# Titan_v1p2.net
KiCad netlist of a schematic drawn in EAGLE
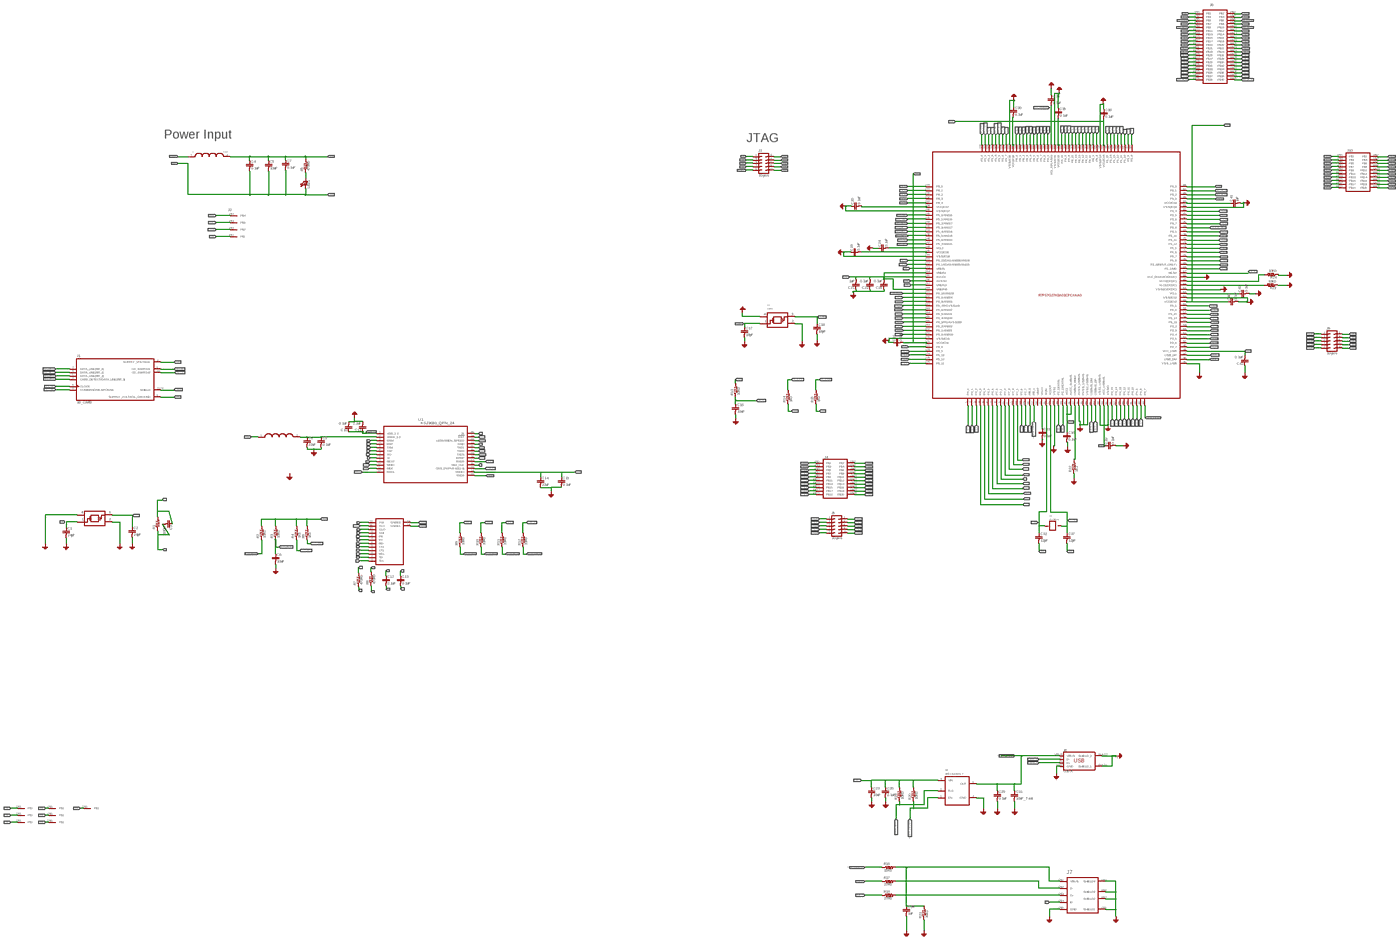
[diagram p0: schematic, sheet 1, overview]
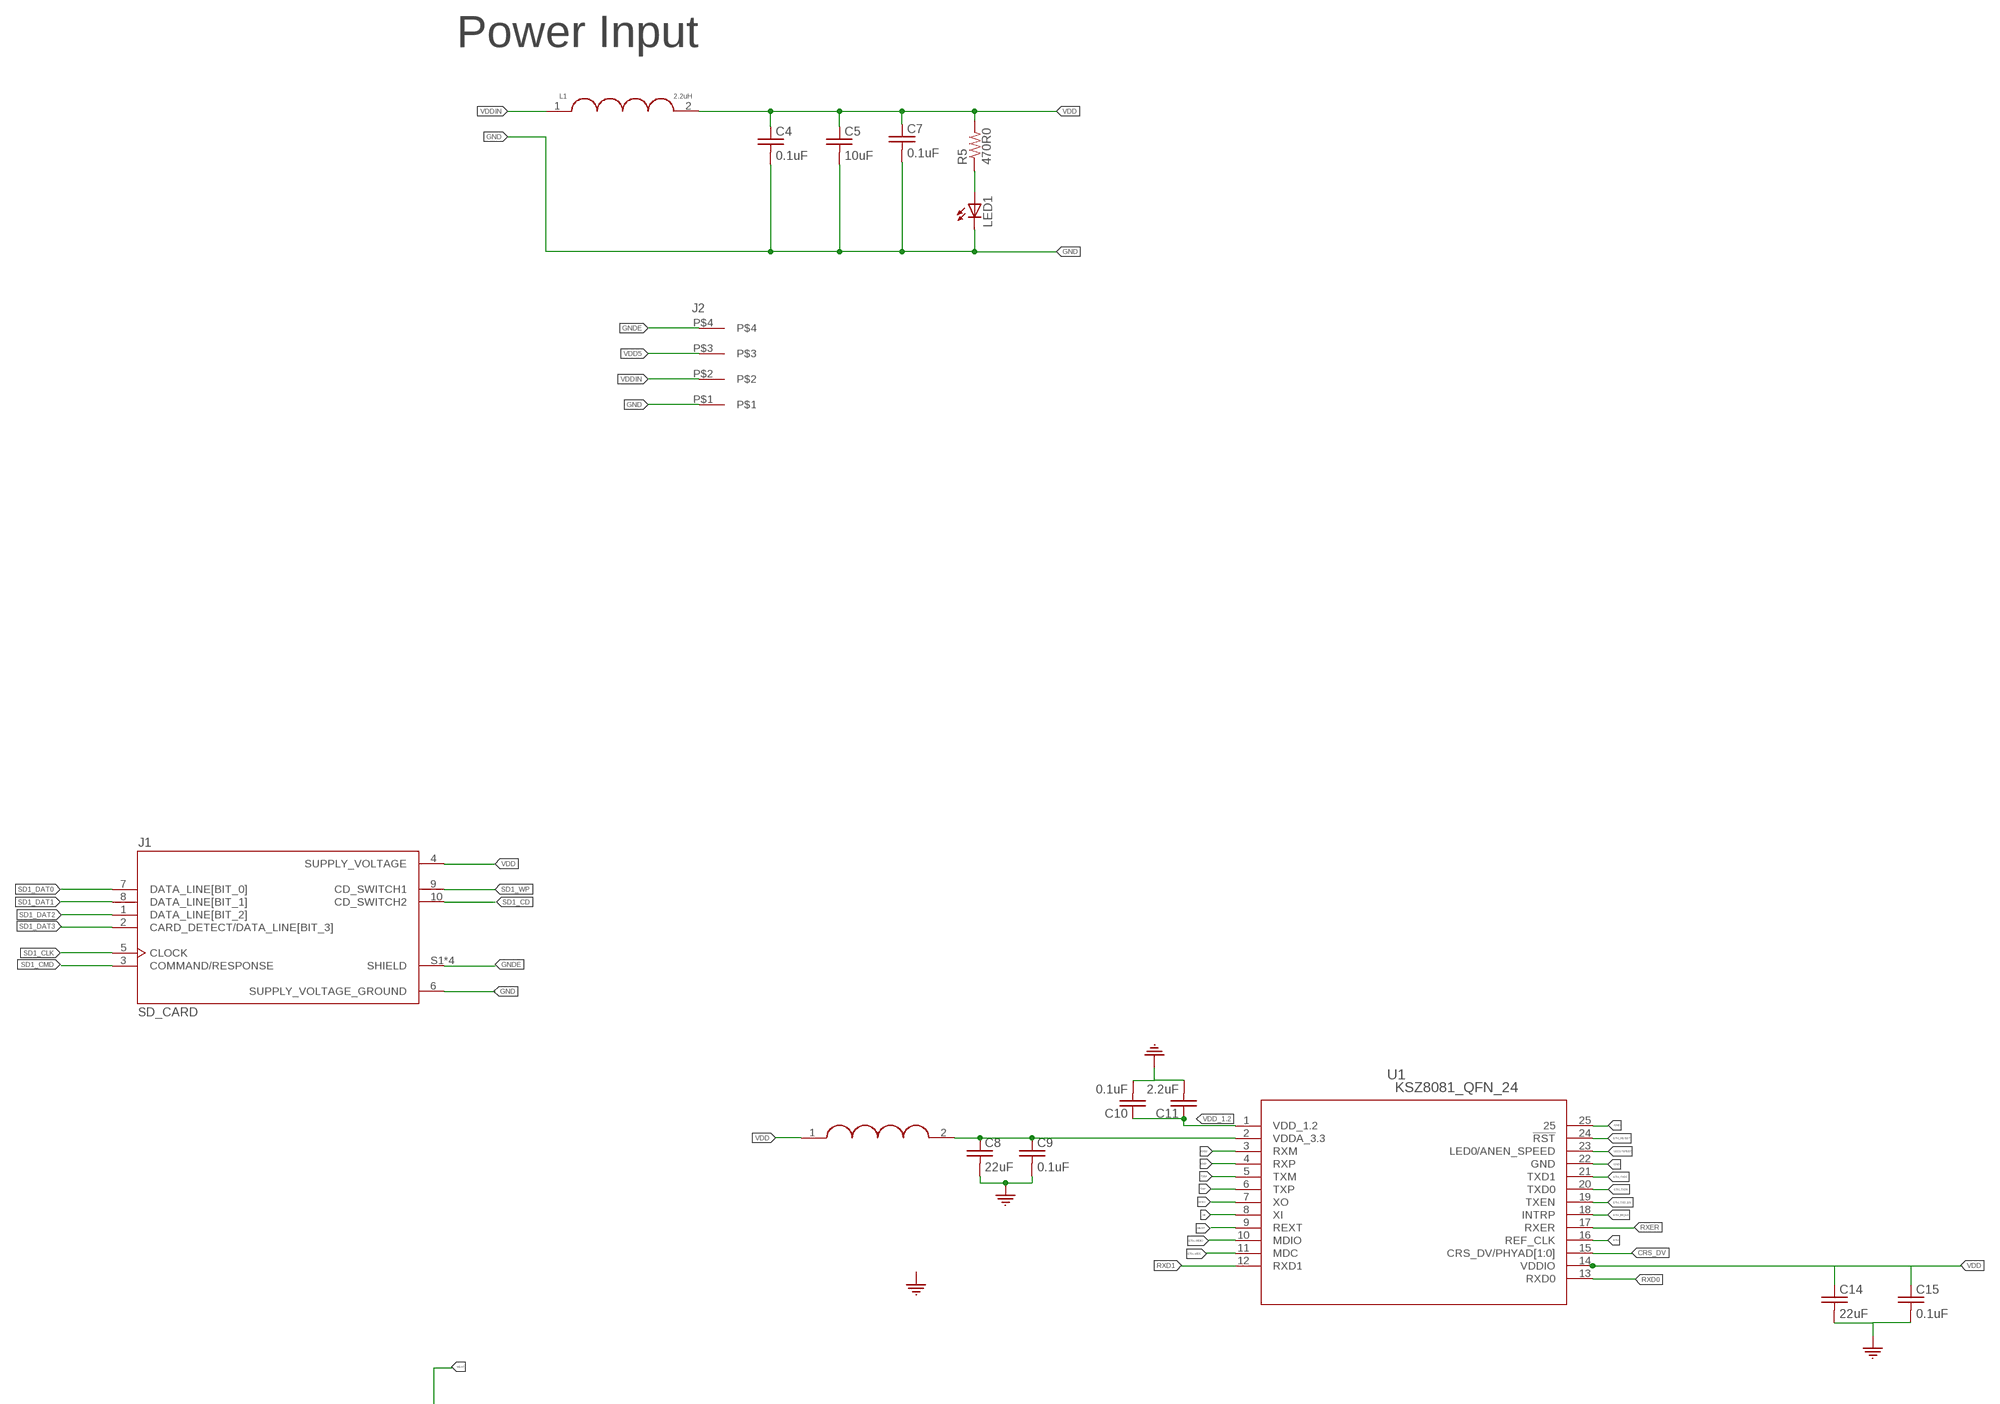
[diagram p1: schematic, sheet 1, part 1 of 5]
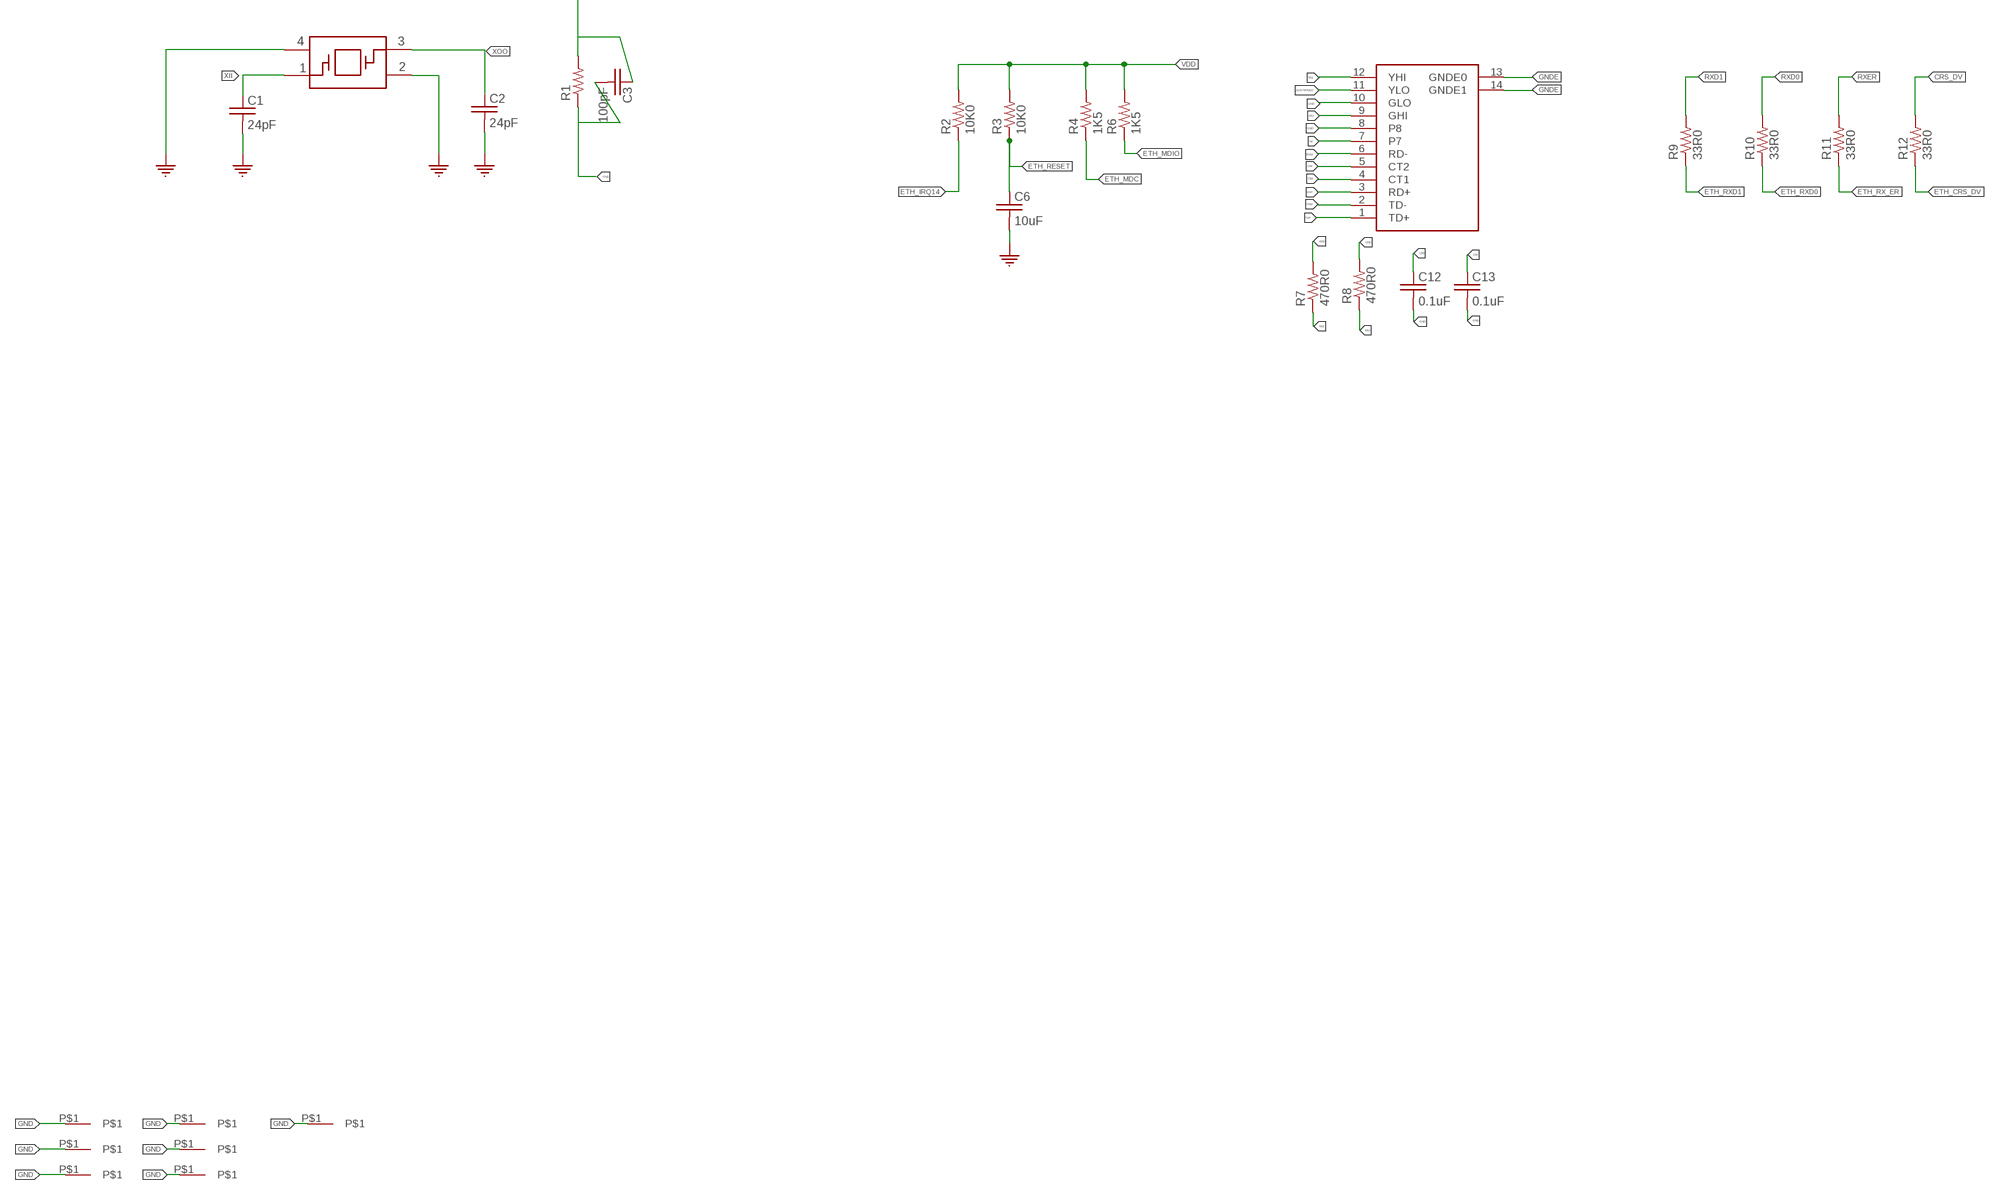
[diagram p2: schematic, sheet 1, part 2 of 5]
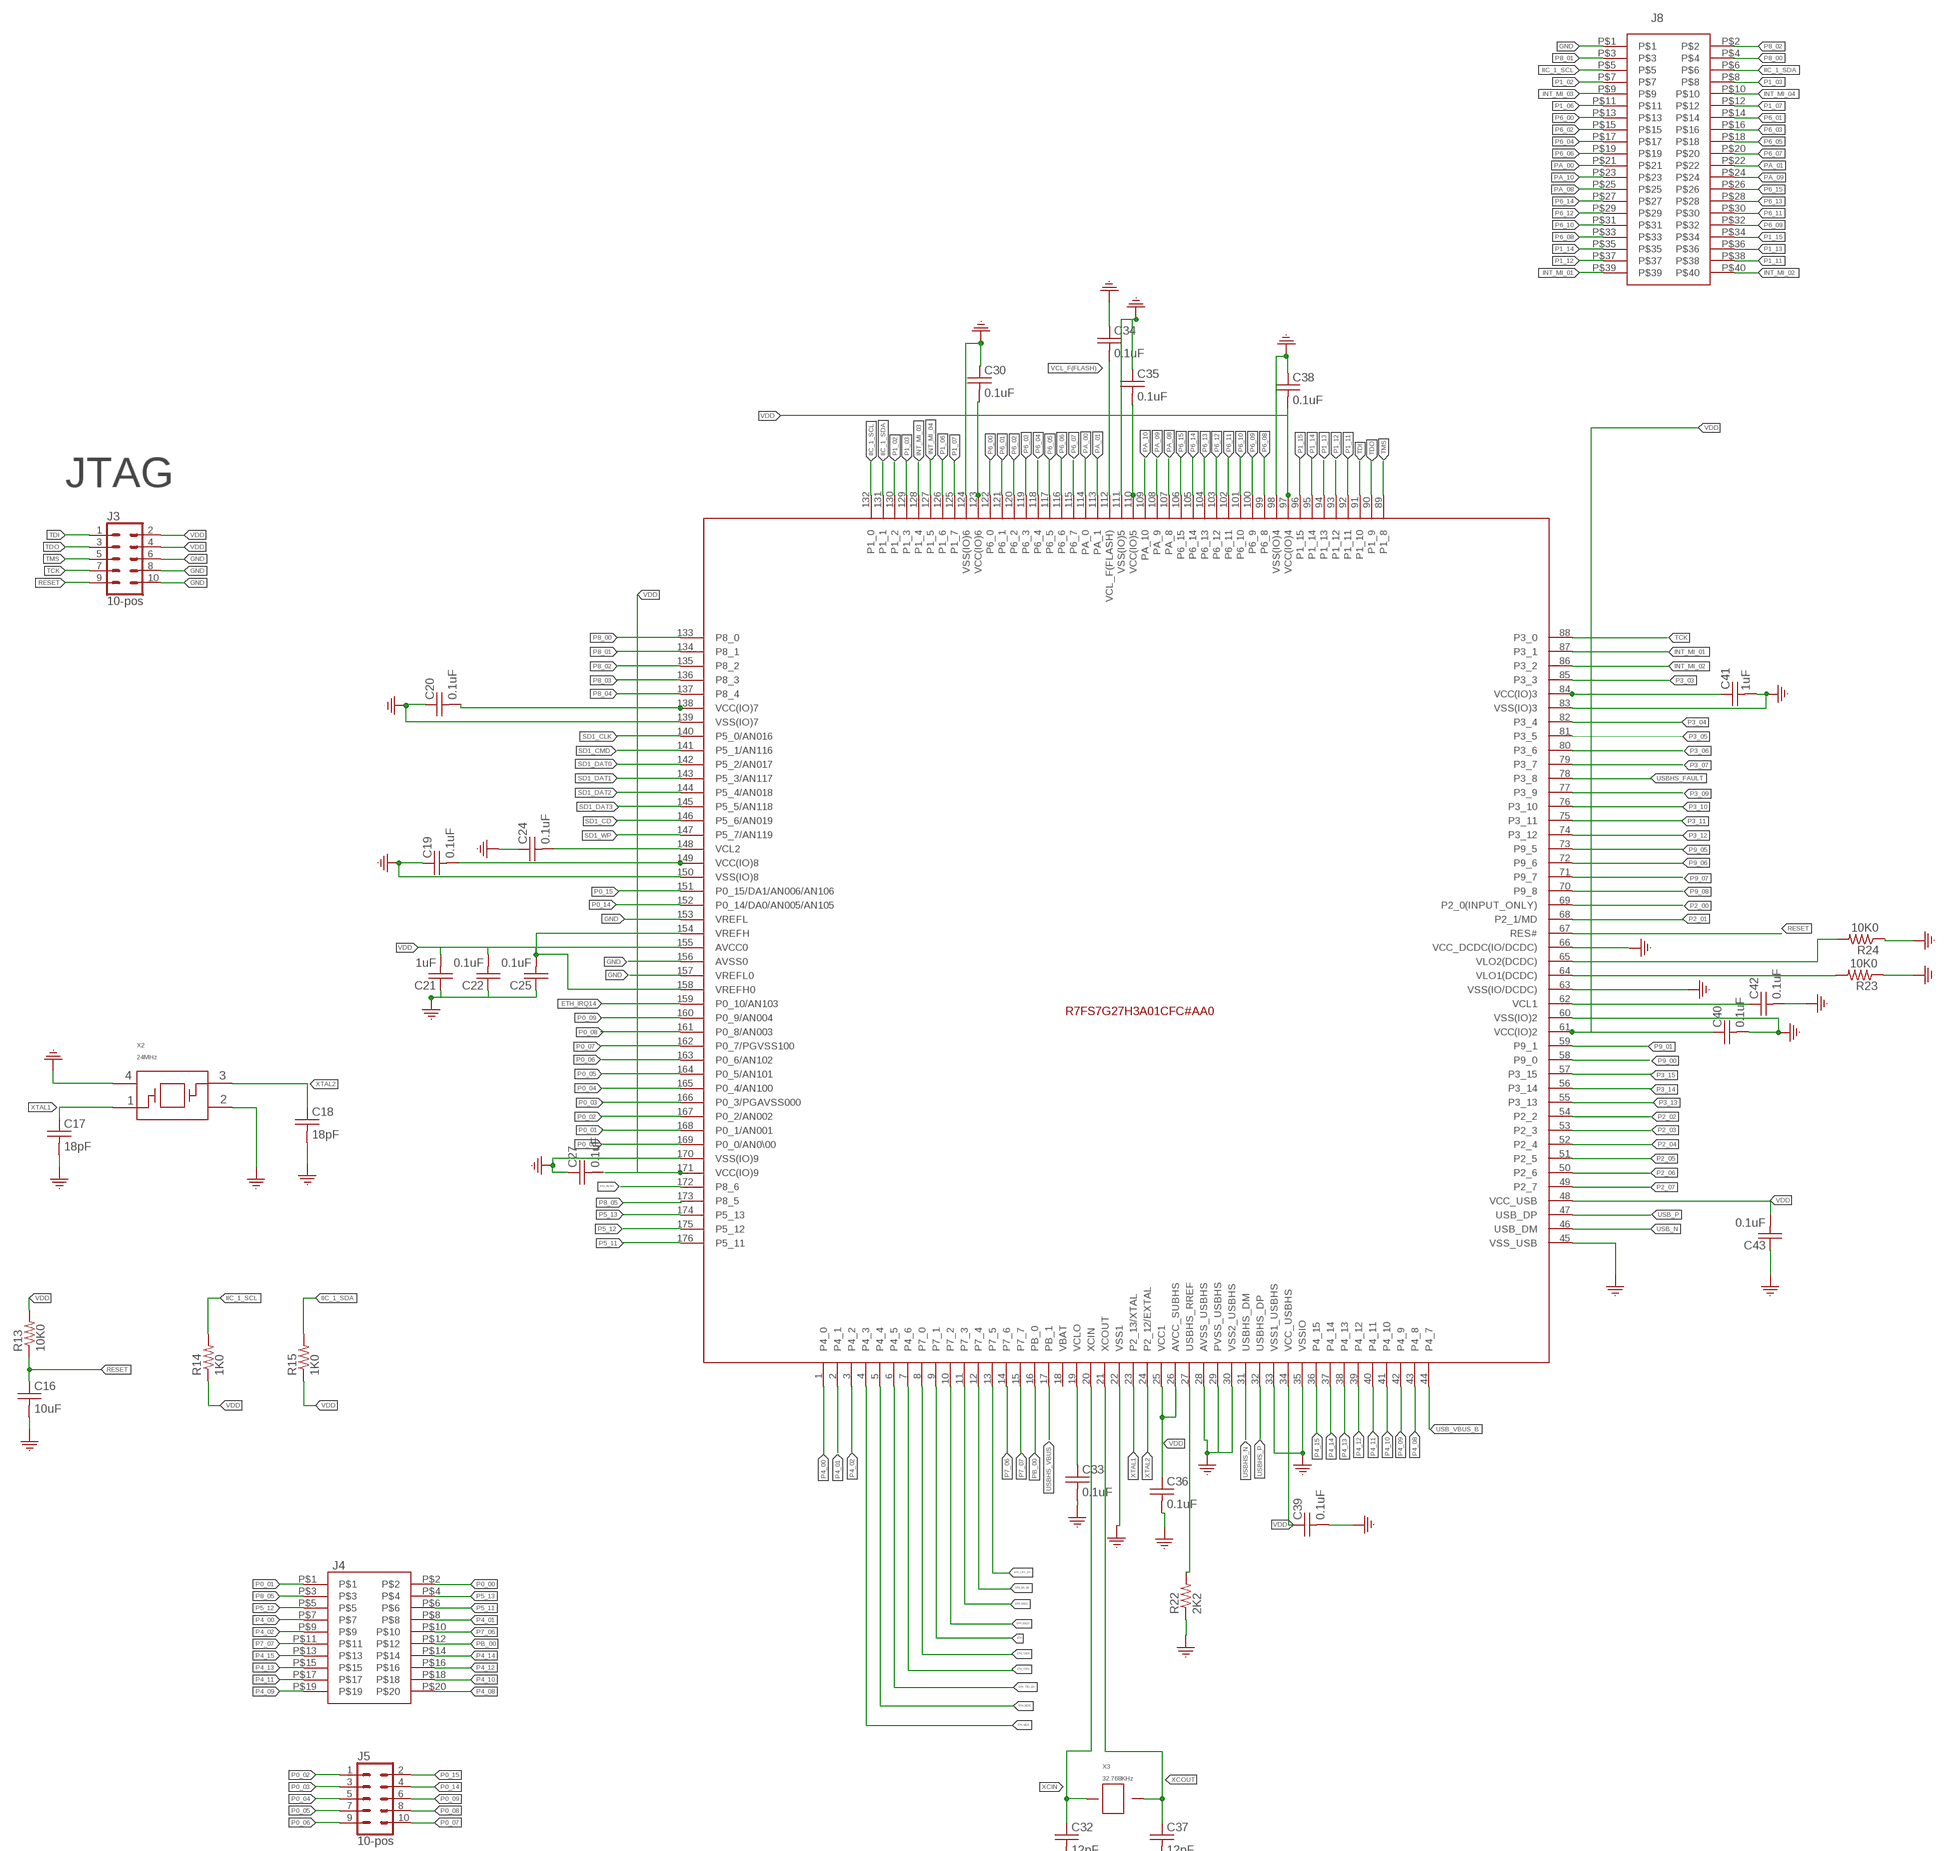
[diagram p3: schematic, sheet 1, part 3 of 5]
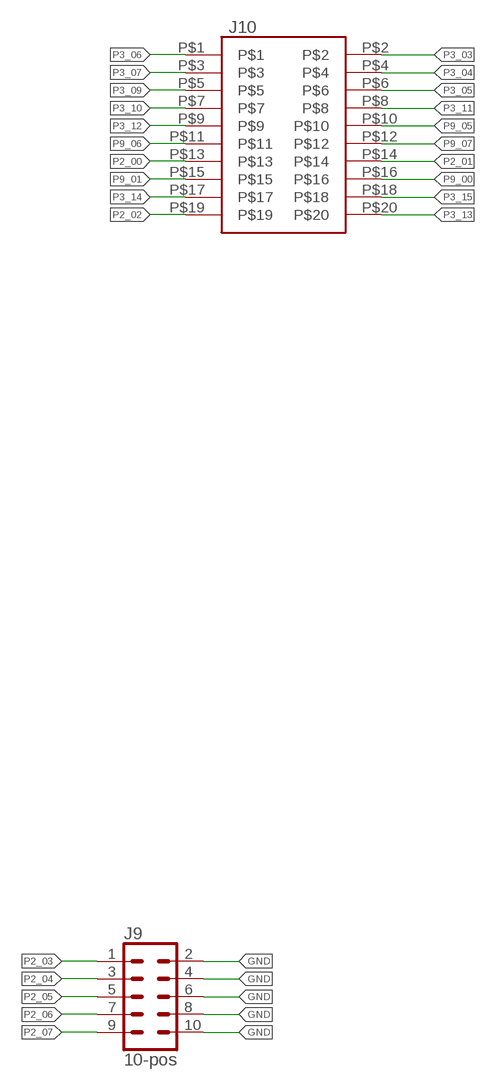
[diagram p4: schematic, sheet 1, part 4 of 5]
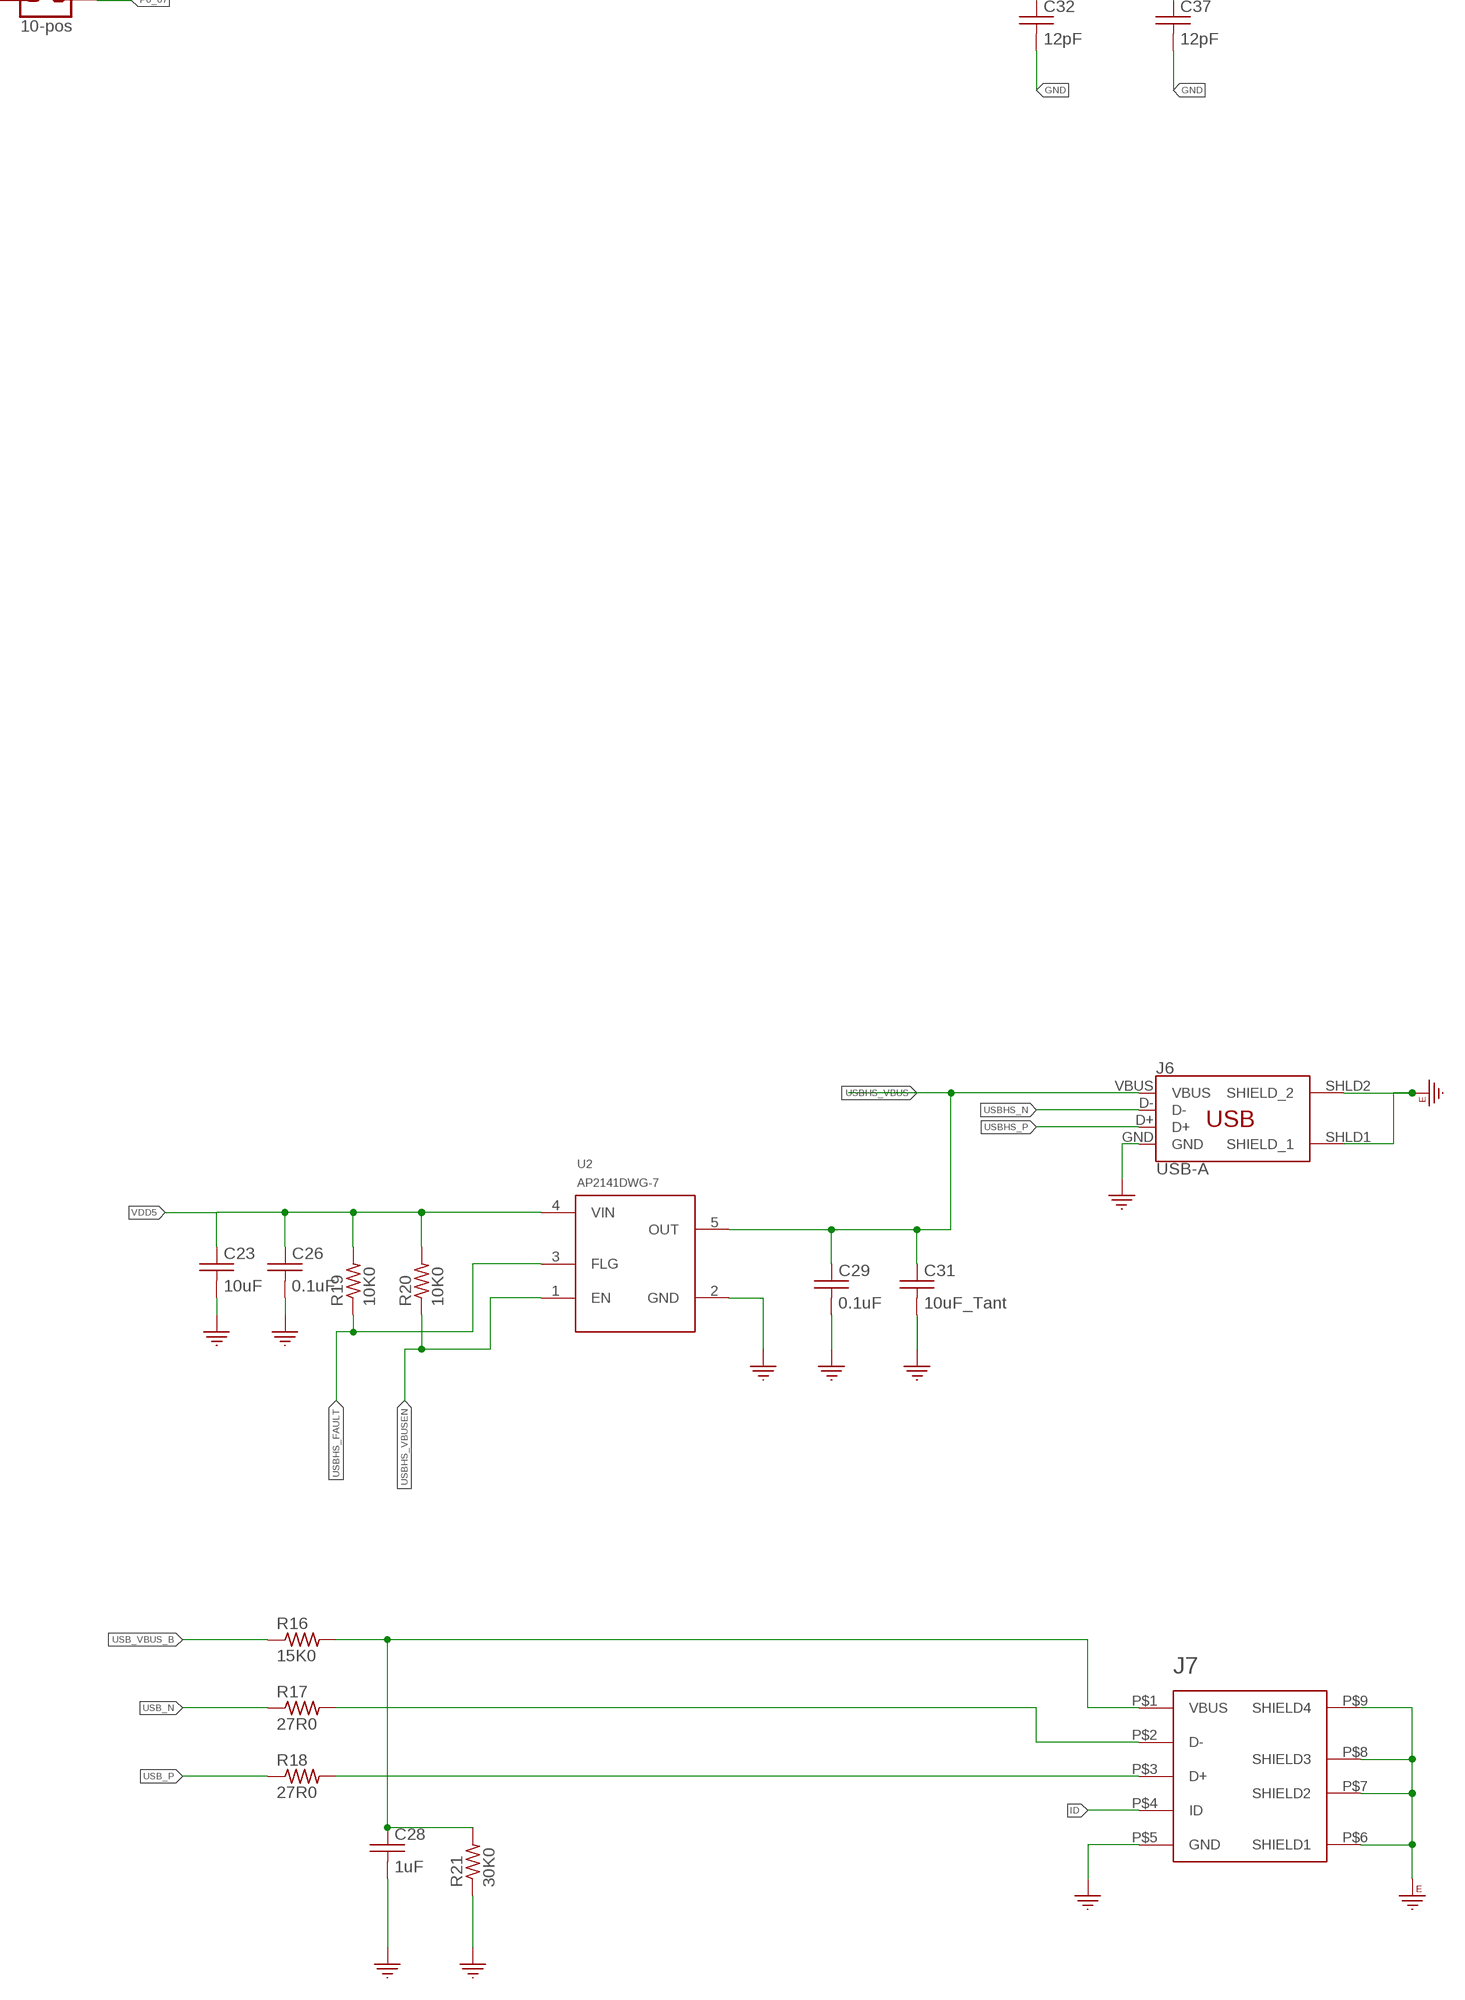
[diagram p5: schematic, sheet 1, part 5 of 5]

(export (version "E")
  (design (tool "Eeschema 10.0.6"))
  (components
    (comp (ref "C1")
      (value "24pF")
      (footprint "eagle-import:0402")
      (fields (field (name "PARTNO") "CC0402GRNPO9BN240"))
      (libsource (lib "eagle-import") (part "C_0402_24PF"))
    )
    (comp (ref "C2")
      (value "24pF")
      (footprint "eagle-import:0402")
      (fields (field (name "PARTNO") "CC0402GRNPO9BN240"))
      (libsource (lib "eagle-import") (part "C_0402_24PF"))
    )
    (comp (ref "C3")
      (value "100pF")
      (footprint "eagle-import:0402")
      (fields (field (name "PARTNO") "CL05C101JB5NNNC"))
      (libsource (lib "eagle-import") (part "C_0402_100PF"))
    )
    (comp (ref "C4")
      (value "0.1uF")
      (footprint "eagle-import:0402")
      (fields (field (name "PARTNO") "CL05F104ZO5NNNC"))
      (libsource (lib "eagle-import") (part "C_0402_0.1UF"))
    )
    (comp (ref "C5")
      (value "10uF")
      (footprint "eagle-import:0402")
      (fields (field (name "PARTNO") "CL05A106MP8NUB8"))
      (libsource (lib "eagle-import") (part "C_0402_10UF"))
    )
    (comp (ref "C6")
      (value "10uF")
      (footprint "eagle-import:0402")
      (fields (field (name "PARTNO") "CL05A106MP8NUB8"))
      (libsource (lib "eagle-import") (part "C_0402_10UF"))
    )
    (comp (ref "C7")
      (value "0.1uF")
      (footprint "eagle-import:0402")
      (fields (field (name "PARTNO") "CL05F104ZO5NNNC"))
      (libsource (lib "eagle-import") (part "C_0402_0.1UF"))
    )
    (comp (ref "C8")
      (value "22uF")
      (footprint "eagle-import:0402")
      (fields (field (name "PARTNO") "CL05A226MQ5N6J8"))
      (libsource (lib "eagle-import") (part "C_0402_22UF"))
    )
    (comp (ref "C9")
      (value "0.1uF")
      (footprint "eagle-import:0402")
      (fields (field (name "PARTNO") "CL05F104ZO5NNNC"))
      (libsource (lib "eagle-import") (part "C_0402_0.1UF"))
    )
    (comp (ref "C10")
      (value "0.1uF")
      (footprint "eagle-import:0402")
      (fields (field (name "PARTNO") "CL05F104ZO5NNNC"))
      (libsource (lib "eagle-import") (part "C_0402_0.1UF"))
    )
    (comp (ref "C11")
      (value "2.2uF")
      (footprint "eagle-import:0402")
      (fields (field (name "PARTNO") "GRM155C81C225ME15D"))
      (libsource (lib "eagle-import") (part "C_0402_2.2UF"))
    )
    (comp (ref "C12")
      (value "0.1uF")
      (footprint "eagle-import:0402")
      (fields (field (name "PARTNO") "CL05F104ZO5NNNC"))
      (libsource (lib "eagle-import") (part "C_0402_0.1UF"))
    )
    (comp (ref "C13")
      (value "0.1uF")
      (footprint "eagle-import:0402")
      (fields (field (name "PARTNO") "CL05F104ZO5NNNC"))
      (libsource (lib "eagle-import") (part "C_0402_0.1UF"))
    )
    (comp (ref "C14")
      (value "22uF")
      (footprint "eagle-import:0402")
      (fields (field (name "PARTNO") "CL05A226MQ5N6J8"))
      (libsource (lib "eagle-import") (part "C_0402_22UF"))
    )
    (comp (ref "C15")
      (value "0.1uF")
      (footprint "eagle-import:0402")
      (fields (field (name "PARTNO") "CL05F104ZO5NNNC"))
      (libsource (lib "eagle-import") (part "C_0402_0.1UF"))
    )
    (comp (ref "C16")
      (value "10uF")
      (footprint "eagle-import:0402")
      (fields (field (name "PARTNO") "CL05A106MP8NUB8"))
      (libsource (lib "eagle-import") (part "C_0402_10UF"))
    )
    (comp (ref "C17")
      (value "18pF")
      (footprint "eagle-import:0402")
      (fields (field (name "PARTNO") "UMK105CG180JV-F"))
      (libsource (lib "eagle-import") (part "C_0402_18PF"))
    )
    (comp (ref "C18")
      (value "18pF")
      (footprint "eagle-import:0402")
      (fields (field (name "PARTNO") "UMK105CG180JV-F"))
      (libsource (lib "eagle-import") (part "C_0402_18PF"))
    )
    (comp (ref "C19")
      (value "0.1uF")
      (footprint "eagle-import:0402")
      (fields (field (name "PARTNO") "CL05F104ZO5NNNC"))
      (libsource (lib "eagle-import") (part "C_0402_0.1UF"))
    )
    (comp (ref "C20")
      (value "0.1uF")
      (footprint "eagle-import:0402")
      (fields (field (name "PARTNO") "CL05F104ZO5NNNC"))
      (libsource (lib "eagle-import") (part "C_0402_0.1UF"))
    )
    (comp (ref "C21")
      (value "1uF")
      (footprint "eagle-import:0402")
      (fields (field (name "PARTNO") "CL05A105KO5NNNC"))
      (libsource (lib "eagle-import") (part "C_0402_1UF"))
    )
    (comp (ref "C22")
      (value "0.1uF")
      (footprint "eagle-import:0402")
      (fields (field (name "PARTNO") "CL05F104ZO5NNNC"))
      (libsource (lib "eagle-import") (part "C_0402_0.1UF"))
    )
    (comp (ref "C23")
      (value "10uF")
      (footprint "eagle-import:0402")
      (fields (field (name "PARTNO") "CL05A106MP8NUB8"))
      (libsource (lib "eagle-import") (part "C_0402_10UF"))
    )
    (comp (ref "C24")
      (value "0.1uF")
      (footprint "eagle-import:0402")
      (fields (field (name "PARTNO") "CL05F104ZO5NNNC"))
      (libsource (lib "eagle-import") (part "C_0402_0.1UF"))
    )
    (comp (ref "C25")
      (value "0.1uF")
      (footprint "eagle-import:0402")
      (fields (field (name "PARTNO") "CL05F104ZO5NNNC"))
      (libsource (lib "eagle-import") (part "C_0402_0.1UF"))
    )
    (comp (ref "C26")
      (value "0.1uF")
      (footprint "eagle-import:0402")
      (fields (field (name "PARTNO") "CL05F104ZO5NNNC"))
      (libsource (lib "eagle-import") (part "C_0402_0.1UF"))
    )
    (comp (ref "C27")
      (value "0.1uF")
      (footprint "eagle-import:0402")
      (fields (field (name "PARTNO") "CL05F104ZO5NNNC"))
      (libsource (lib "eagle-import") (part "C_0402_0.1UF"))
    )
    (comp (ref "C28")
      (value "1uF")
      (footprint "eagle-import:0402")
      (fields (field (name "PARTNO") "CL05A105KO5NNNC"))
      (libsource (lib "eagle-import") (part "C_0402_1UF"))
    )
    (comp (ref "C29")
      (value "0.1uF")
      (footprint "eagle-import:0402")
      (fields (field (name "PARTNO") "CL05F104ZO5NNNC"))
      (libsource (lib "eagle-import") (part "C_0402_0.1UF"))
    )
    (comp (ref "C30")
      (value "0.1uF")
      (footprint "eagle-import:0402")
      (fields (field (name "PARTNO") "CL05F104ZO5NNNC"))
      (libsource (lib "eagle-import") (part "C_0402_0.1UF"))
    )
    (comp (ref "C31")
      (value "10uF_Tant")
      (footprint "eagle-import:C1210")
      (fields (field (name "PARTNO") "TPST106K016H0800"))
      (libsource (lib "eagle-import") (part "C_1210_10UF_TANT"))
    )
    (comp (ref "C32")
      (value "12pF")
      (footprint "eagle-import:0402")
      (fields (field (name "PARTNO") "CL05C120JB5NNNC"))
      (libsource (lib "eagle-import") (part "C_0402_12PF"))
    )
    (comp (ref "C33")
      (value "0.1uF")
      (footprint "eagle-import:0402")
      (fields (field (name "PARTNO") "CL05F104ZO5NNNC"))
      (libsource (lib "eagle-import") (part "C_0402_0.1UF"))
    )
    (comp (ref "C34")
      (value "0.1uF")
      (footprint "eagle-import:0402")
      (fields (field (name "PARTNO") "CL05F104ZO5NNNC"))
      (libsource (lib "eagle-import") (part "C_0402_0.1UF"))
    )
    (comp (ref "C35")
      (value "0.1uF")
      (footprint "eagle-import:0402")
      (fields (field (name "PARTNO") "CL05F104ZO5NNNC"))
      (libsource (lib "eagle-import") (part "C_0402_0.1UF"))
    )
    (comp (ref "C36")
      (value "0.1uF")
      (footprint "eagle-import:0402")
      (fields (field (name "PARTNO") "CL05F104ZO5NNNC"))
      (libsource (lib "eagle-import") (part "C_0402_0.1UF"))
    )
    (comp (ref "C37")
      (value "12pF")
      (footprint "eagle-import:0402")
      (fields (field (name "PARTNO") "CL05C120JB5NNNC"))
      (libsource (lib "eagle-import") (part "C_0402_12PF"))
    )
    (comp (ref "C38")
      (value "0.1uF")
      (footprint "eagle-import:0402")
      (fields (field (name "PARTNO") "CL05F104ZO5NNNC"))
      (libsource (lib "eagle-import") (part "C_0402_0.1UF"))
    )
    (comp (ref "C39")
      (value "0.1uF")
      (footprint "eagle-import:0402")
      (fields (field (name "PARTNO") "CL05F104ZO5NNNC"))
      (libsource (lib "eagle-import") (part "C_0402_0.1UF"))
    )
    (comp (ref "C40")
      (value "0.1uF")
      (footprint "eagle-import:0402")
      (fields (field (name "PARTNO") "CL05F104ZO5NNNC"))
      (libsource (lib "eagle-import") (part "C_0402_0.1UF"))
    )
    (comp (ref "C41")
      (value "1uF")
      (footprint "eagle-import:0402")
      (fields (field (name "PARTNO") "CL05A105KO5NNNC"))
      (libsource (lib "eagle-import") (part "C_0402_1UF"))
    )
    (comp (ref "C42")
      (value "0.1uF")
      (footprint "eagle-import:0402")
      (fields (field (name "PARTNO") "CL05F104ZO5NNNC"))
      (libsource (lib "eagle-import") (part "C_0402_0.1UF"))
    )
    (comp (ref "C43")
      (value "0.1uF")
      (footprint "eagle-import:0402")
      (fields (field (name "PARTNO") "CL05F104ZO5NNNC"))
      (libsource (lib "eagle-import") (part "C_0402_0.1UF"))
    )
    (comp (ref "FB1")
      (value "FB2_603")
      (footprint "eagle-import:0603")
      (fields (field (name "PARTNO") "BLM18PG121SN1D"))
      (libsource (lib "eagle-import") (part "FB_0603_120_OHM0603"))
    )
    (comp (ref "FID1")
      (value "FIDUCIAL")
      (footprint "eagle-import:FIDUCIAL")
      (libsource (lib "eagle-import") (part "FIDUCIAL"))
    )
    (comp (ref "FID2")
      (value "FIDUCIAL")
      (footprint "eagle-import:FIDUCIAL")
      (libsource (lib "eagle-import") (part "FIDUCIAL"))
    )
    (comp (ref "FID3")
      (value "FIDUCIAL")
      (footprint "eagle-import:FIDUCIAL")
      (libsource (lib "eagle-import") (part "FIDUCIAL"))
    )
    (comp (ref "FID4")
      (value "FIDUCIAL")
      (footprint "eagle-import:FIDUCIAL")
      (libsource (lib "eagle-import") (part "FIDUCIAL"))
    )
    (comp (ref "FID5")
      (value "FIDUCIAL")
      (footprint "eagle-import:FIDUCIAL")
      (libsource (lib "eagle-import") (part "FIDUCIAL"))
    )
    (comp (ref "FID6")
      (value "FIDUCIAL")
      (footprint "eagle-import:FIDUCIAL")
      (libsource (lib "eagle-import") (part "FIDUCIAL"))
    )
    (comp (ref "FID7")
      (value "FIDUCIAL")
      (footprint "eagle-import:FIDUCIAL")
      (libsource (lib "eagle-import") (part "FIDUCIAL"))
    )
    (comp (ref "J1")
      (value "SD_CARD")
      (footprint "eagle-import:SD_CARD")
      (fields (field (name "MF") "Amphenol ICC") (field (name "PARTNO") "114-00841-68"))
      (libsource (lib "eagle-import") (part "SD_CARD_1140084168"))
    )
    (comp (ref "J2")
      (value "4-pos")
      (footprint "eagle-import:1X4_3.81MM_PITCH")
      (fields (field (name "PARTNO") "691322310004"))
      (libsource (lib "eagle-import") (part "3.81MM_1_X_4_RT_ANGLE_PLUG_HEADER"))
    )
    (comp (ref "J3")
      (value "10-pos")
      (footprint "eagle-import:2X5")
      (fields (field (name "PARTNO") "PH2RA-10-UA"))
      (libsource (lib "eagle-import") (part "CONN_05X2_RAPTH"))
    )
    (comp (ref "J4")
      (value "20-pos")
      (footprint "eagle-import:2_X_10_.1_INCH")
      (fields (field (name "PARTNO") "67996-420HLF"))
      (libsource (lib "eagle-import") (part "2_X_10_HEADER_GENERIC"))
    )
    (comp (ref "J5")
      (value "10-pos")
      (footprint "eagle-import:2X5")
      (fields (field (name "PARTNO") "PH2RA-10-UA"))
      (libsource (lib "eagle-import") (part "CONN_05X2_RAPTH"))
    )
    (comp (ref "J6")
      (value "USB-A")
      (footprint "eagle-import:USB_A_SMT")
      (fields (field (name "PARTNO") "87583-3010RPALF"))
      (libsource (lib "eagle-import") (part "USB_A"))
    )
    (comp (ref "J7")
      (value "USB-B-Micro")
      (footprint "eagle-import:USB_MICRO-B")
      (fields (field (name "PARTNO") "10118192-0002LF"))
      (libsource (lib "eagle-import") (part "USB_MICRO-B"))
    )
    (comp (ref "J8")
      (value "40-pos")
      (footprint "eagle-import:HEADER_2_X_20_.1_INCH")
      (fields (field (name "PARTNO") "61304021021"))
      (libsource (lib "eagle-import") (part "HEADER_2_X_20_GENERIC"))
    )
    (comp (ref "J9")
      (value "10-pos")
      (footprint "eagle-import:2X5")
      (fields (field (name "PARTNO") "PH2RA-10-UA"))
      (libsource (lib "eagle-import") (part "CONN_05X2_RAPTH"))
    )
    (comp (ref "J10")
      (value "20-pos")
      (footprint "eagle-import:2_X_10_.1_INCH")
      (fields (field (name "PARTNO") "67996-420HLF"))
      (libsource (lib "eagle-import") (part "2_X_10_HEADER_GENERIC"))
    )
    (comp (ref "L1")
      (value "2.2uH")
      (footprint "eagle-import:1008")
      (fields (field (name "PARTNO") "LQM2HPN2R2MG0L"))
      (libsource (lib "eagle-import") (part "INDUCTOR_1008_2.2_MH_1.3A"))
    )
    (comp (ref "LED1")
      (value "Green")
      (footprint "eagle-import:0805")
      (fields (field (name "PARTNO") "LG R971-KN-1"))
      (libsource (lib "eagle-import") (part "LED_0805_GREEN"))
    )
    (comp (ref "R1")
      (value "6K49")
      (footprint "eagle-import:0402")
      (fields (field (name "PARTNO") "RMCF0402FT6K49"))
      (libsource (lib "eagle-import") (part "R_0402_6K49"))
    )
    (comp (ref "R2")
      (value "10K0")
      (footprint "eagle-import:0402")
      (fields (field (name "PARTNO") "RMCF0402JT10K0"))
      (libsource (lib "eagle-import") (part "R_0402_10K0"))
    )
    (comp (ref "R3")
      (value "10K0")
      (footprint "eagle-import:0402")
      (fields (field (name "PARTNO") "RMCF0402JT10K0"))
      (libsource (lib "eagle-import") (part "R_0402_10K0"))
    )
    (comp (ref "R4")
      (value "1K5")
      (footprint "eagle-import:0402")
      (fields (field (name "PARTNO") "RMCF0402JT1K50"))
      (libsource (lib "eagle-import") (part "R_0402_1K5"))
    )
    (comp (ref "R5")
      (value "470R0")
      (footprint "eagle-import:0402")
      (fields (field (name "PARTNO") "RMCF0402JT470R"))
      (libsource (lib "eagle-import") (part "R_0402_470R0"))
    )
    (comp (ref "R6")
      (value "1K5")
      (footprint "eagle-import:0402")
      (fields (field (name "PARTNO") "RMCF0402JT1K50"))
      (libsource (lib "eagle-import") (part "R_0402_1K5"))
    )
    (comp (ref "R7")
      (value "470R0")
      (footprint "eagle-import:0402")
      (fields (field (name "PARTNO") "RMCF0402JT470R"))
      (libsource (lib "eagle-import") (part "R_0402_470R0"))
    )
    (comp (ref "R8")
      (value "470R0")
      (footprint "eagle-import:0402")
      (fields (field (name "PARTNO") "RMCF0402JT470R"))
      (libsource (lib "eagle-import") (part "R_0402_470R0"))
    )
    (comp (ref "R9")
      (value "33R0")
      (footprint "eagle-import:0402")
      (fields (field (name "PARTNO") "RMCF0402JT33R0"))
      (libsource (lib "eagle-import") (part "R_0402_33R0"))
    )
    (comp (ref "R10")
      (value "33R0")
      (footprint "eagle-import:0402")
      (fields (field (name "PARTNO") "RMCF0402JT33R0"))
      (libsource (lib "eagle-import") (part "R_0402_33R0"))
    )
    (comp (ref "R11")
      (value "33R0")
      (footprint "eagle-import:0402")
      (fields (field (name "PARTNO") "RMCF0402JT33R0"))
      (libsource (lib "eagle-import") (part "R_0402_33R0"))
    )
    (comp (ref "R12")
      (value "33R0")
      (footprint "eagle-import:0402")
      (fields (field (name "PARTNO") "RMCF0402JT33R0"))
      (libsource (lib "eagle-import") (part "R_0402_33R0"))
    )
    (comp (ref "R13")
      (value "10K0")
      (footprint "eagle-import:0402")
      (fields (field (name "PARTNO") "RMCF0402JT10K0"))
      (libsource (lib "eagle-import") (part "R_0402_10K0"))
    )
    (comp (ref "R14")
      (value "1K0")
      (footprint "eagle-import:0402")
      (fields (field (name "PARTNO") "CRG0402J1K0"))
      (libsource (lib "eagle-import") (part "R_0402_1K0"))
    )
    (comp (ref "R15")
      (value "1K0")
      (footprint "eagle-import:0402")
      (fields (field (name "PARTNO") "CRG0402J1K0"))
      (libsource (lib "eagle-import") (part "R_0402_1K0"))
    )
    (comp (ref "R16")
      (value "15K0")
      (footprint "eagle-import:0402")
      (fields (field (name "PARTNO") "RMCF0402JT15K0"))
      (libsource (lib "eagle-import") (part "R_0402_15K0"))
    )
    (comp (ref "R17")
      (value "27R0")
      (footprint "eagle-import:0402")
      (fields (field (name "PARTNO") "RMCF0402JT27R0"))
      (libsource (lib "eagle-import") (part "R_0402_27R0"))
    )
    (comp (ref "R18")
      (value "27R0")
      (footprint "eagle-import:0402")
      (fields (field (name "PARTNO") "RMCF0402JT27R0"))
      (libsource (lib "eagle-import") (part "R_0402_27R0"))
    )
    (comp (ref "R19")
      (value "10K0")
      (footprint "eagle-import:0402")
      (fields (field (name "PARTNO") "RMCF0402JT10K0"))
      (libsource (lib "eagle-import") (part "R_0402_10K0"))
    )
    (comp (ref "R20")
      (value "10K0")
      (footprint "eagle-import:0402")
      (fields (field (name "PARTNO") "RMCF0402JT10K0"))
      (libsource (lib "eagle-import") (part "R_0402_10K0"))
    )
    (comp (ref "R21")
      (value "30K0")
      (footprint "eagle-import:0402")
      (fields (field (name "PARTNO") "RC0402JR-0730KL"))
      (libsource (lib "eagle-import") (part "R_0402_30K0"))
    )
    (comp (ref "R22")
      (value "2K2")
      (footprint "eagle-import:0402")
      (fields (field (name "PARTNO") "RMCF0402JT2K20"))
      (libsource (lib "eagle-import") (part "R_0402_2K2"))
    )
    (comp (ref "R23")
      (value "10K0")
      (footprint "eagle-import:0402")
      (fields (field (name "PARTNO") "RMCF0402JT10K0"))
      (libsource (lib "eagle-import") (part "R_0402_10K0"))
    )
    (comp (ref "R24")
      (value "10K0")
      (footprint "eagle-import:0402")
      (fields (field (name "PARTNO") "RMCF0402JT10K0"))
      (libsource (lib "eagle-import") (part "R_0402_10K0"))
    )
    (comp (ref "RJ1")
      (value "RJ45")
      (footprint "eagle-import:RJ45_TH_ELEC")
      (fields (field (name "PARTNO") "13F-64GYD2PL2NL"))
      (libsource (lib "eagle-import") (part "RJ45_WITH_ELEC"))
    )
    (comp (ref "U1")
      (value "KSZ8081_QFN_24")
      (footprint "eagle-import:QFN-24-M")
      (fields (field (name "PARTNO") "KSZ8081RNACA"))
      (libsource (lib "eagle-import") (part "KSZ8081RNACAQFN-24-M"))
    )
    (comp (ref "U2")
      (value "AP2151DWG-7")
      (footprint "eagle-import:SOT-23-5")
      (fields (field (name "PARTNO") "AP2151WG-7"))
      (libsource (lib "eagle-import") (part "AP2151DWG-7"))
    )
    (comp (ref "U3")
      (value "S7G2LQFP176")
      (footprint "eagle-import:LQFP176_24X24")
      (fields (field (name "PARTNO") "R7FS7G27H3A01CFC#AA0"))
      (libsource (lib "eagle-import") (part "S7G2_X_176"))
    )
    (comp (ref "X1")
      (value "25MHz")
      (footprint "eagle-import:SMD_3225")
      (fields (field (name "PARTNO") "FA-238 25.0000MB-B3"))
      (libsource (lib "eagle-import") (part "XTAL_25_MHZ"))
    )
    (comp (ref "X2")
      (value "24MHz")
      (footprint "eagle-import:SMD_3225")
      (fields (field (name "PARTNO") "FA-238 24.0000MB-C3 "))
      (libsource (lib "eagle-import") (part "XTAL_24_MHZ"))
    )
    (comp (ref "X3")
      (value "32.768KHz")
      (footprint "eagle-import:SMD_X_2_PADS")
      (fields (field (name "PARTNO") "ABS07-32.768KHZ-T"))
      (libsource (lib "eagle-import") (part "XTAL_32.768KHZ"))
    )
  )
  (nets
    (net (code "1") (name "C58") (class "Default")
      (node (ref "C12") (pin "P$1") (pinfunction "1_P$1") (pintype "passive"))
      (node (ref "RJ1") (pin "4") (pinfunction "CT1_4") (pintype "bidirectional"))
    )
    (net (code "2") (name "C60") (class "Default")
      (node (ref "C13") (pin "P$1") (pinfunction "1_P$1") (pintype "passive"))
      (node (ref "RJ1") (pin "5") (pinfunction "CT2_5") (pintype "bidirectional"))
    )
    (net (code "3") (name "CRS_DV") (class "Default")
      (node (ref "R12") (pin "P$2") (pinfunction "2_P$2") (pintype "passive"))
      (node (ref "U1") (pin "15") (pinfunction "CRS_DV/PHYAD[1:0]_15") (pintype "bidirectional"))
    )
    (net (code "4") (name "ETH") (class "Default")
      (node (ref "U1") (pin "16") (pinfunction "REF_CLK_16") (pintype "bidirectional"))
      (node (ref "U3") (pin "9") (pinfunction "P7_1_9") (pintype "bidirectional"))
    )
    (net (code "5") (name "ETH_CRS_DV") (class "Default")
      (node (ref "R12") (pin "P$1") (pinfunction "1_P$1") (pintype "passive"))
      (node (ref "U3") (pin "13") (pinfunction "P7_5_13") (pintype "bidirectional"))
    )
    (net (code "6") (name "ETH_IRQ14") (class "Default")
      (node (ref "R2") (pin "P$1") (pinfunction "1_P$1") (pintype "passive"))
      (node (ref "U1") (pin "18") (pinfunction "INTRP_18") (pintype "bidirectional"))
      (node (ref "U3") (pin "159") (pinfunction "P0_10/AN103_159") (pintype "bidirectional"))
    )
    (net (code "7") (name "ETH_MDC") (class "Default")
      (node (ref "R4") (pin "P$1") (pinfunction "1_P$1") (pintype "passive"))
      (node (ref "U1") (pin "11") (pinfunction "MDC_11") (pintype "input"))
      (node (ref "U3") (pin "4") (pinfunction "P4_3_4") (pintype "bidirectional"))
    )
    (net (code "8") (name "ETH_MDIO") (class "Default")
      (node (ref "R6") (pin "P$1") (pinfunction "1_P$1") (pintype "passive"))
      (node (ref "U1") (pin "10") (pinfunction "MDIO_10") (pintype "bidirectional"))
      (node (ref "U3") (pin "5") (pinfunction "P4_4_5") (pintype "bidirectional"))
    )
    (net (code "9") (name "ETH_RESET") (class "Default")
      (node (ref "C6") (pin "P$1") (pinfunction "1_P$1") (pintype "passive"))
      (node (ref "R3") (pin "P$1") (pinfunction "1_P$1") (pintype "passive"))
      (node (ref "U1") (pin "24") (pinfunction "~{RST}_24") (pintype "input"))
      (node (ref "U3") (pin "172") (pinfunction "P8_6_172") (pintype "bidirectional"))
    )
    (net (code "10") (name "ETH_RXD0") (class "Default")
      (node (ref "R10") (pin "P$1") (pinfunction "1_P$1") (pintype "passive"))
      (node (ref "U3") (pin "10") (pinfunction "P7_2_10") (pintype "bidirectional"))
    )
    (net (code "11") (name "ETH_RXD1") (class "Default")
      (node (ref "R9") (pin "P$1") (pinfunction "1_P$1") (pintype "passive"))
      (node (ref "U3") (pin "11") (pinfunction "P7_3_11") (pintype "bidirectional"))
    )
    (net (code "12") (name "ETH_RX_ER") (class "Default")
      (node (ref "R11") (pin "P$1") (pinfunction "1_P$1") (pintype "passive"))
      (node (ref "U3") (pin "12") (pinfunction "P7_4_12") (pintype "bidirectional"))
    )
    (net (code "13") (name "ETH_TXD0") (class "Default")
      (node (ref "U1") (pin "20") (pinfunction "TXD0_20") (pintype "input"))
      (node (ref "U3") (pin "8") (pinfunction "P7_0_8") (pintype "bidirectional"))
    )
    (net (code "14") (name "ETH_TXD1") (class "Default")
      (node (ref "U1") (pin "21") (pinfunction "TXD1_21") (pintype "bidirectional"))
      (node (ref "U3") (pin "7") (pinfunction "P4_6_7") (pintype "bidirectional"))
    )
    (net (code "15") (name "ETH_TXD_EN") (class "Default")
      (node (ref "U1") (pin "19") (pinfunction "TXEN_19") (pintype "input"))
      (node (ref "U3") (pin "6") (pinfunction "P4_5_6") (pintype "bidirectional"))
    )
    (net (code "16") (name "GND") (class "Default")
      (node (ref "C1") (pin "P$2") (pinfunction "2_P$2") (pintype "passive"))
      (node (ref "C10") (pin "P$2") (pinfunction "2_P$2") (pintype "passive"))
      (node (ref "C11") (pin "P$2") (pinfunction "2_P$2") (pintype "passive"))
      (node (ref "C12") (pin "P$2") (pinfunction "2_P$2") (pintype "passive"))
      (node (ref "C13") (pin "P$2") (pinfunction "2_P$2") (pintype "passive"))
      (node (ref "C14") (pin "P$2") (pinfunction "2_P$2") (pintype "passive"))
      (node (ref "C15") (pin "P$2") (pinfunction "2_P$2") (pintype "passive"))
      (node (ref "C16") (pin "P$2") (pinfunction "2_P$2") (pintype "passive"))
      (node (ref "C17") (pin "P$2") (pinfunction "2_P$2") (pintype "passive"))
      (node (ref "C18") (pin "P$2") (pinfunction "2_P$2") (pintype "passive"))
      (node (ref "C19") (pin "P$1") (pinfunction "1_P$1") (pintype "passive"))
      (node (ref "C2") (pin "P$2") (pinfunction "2_P$2") (pintype "passive"))
      (node (ref "C20") (pin "P$1") (pinfunction "1_P$1") (pintype "passive"))
      (node (ref "C21") (pin "P$1") (pinfunction "1_P$1") (pintype "passive"))
      (node (ref "C22") (pin "P$1") (pinfunction "1_P$1") (pintype "passive"))
      (node (ref "C23") (pin "P$2") (pinfunction "2_P$2") (pintype "passive"))
      (node (ref "C24") (pin "P$1") (pinfunction "1_P$1") (pintype "passive"))
      (node (ref "C25") (pin "P$1") (pinfunction "1_P$1") (pintype "passive"))
      (node (ref "C26") (pin "P$2") (pinfunction "2_P$2") (pintype "passive"))
      (node (ref "C27") (pin "P$1") (pinfunction "1_P$1") (pintype "passive"))
      (node (ref "C28") (pin "P$2") (pinfunction "2_P$2") (pintype "passive"))
      (node (ref "C29") (pin "P$2") (pinfunction "2_P$2") (pintype "passive"))
      (node (ref "C3") (pin "P$2") (pinfunction "2_P$2") (pintype "passive"))
      (node (ref "C30") (pin "P$1") (pinfunction "1_P$1") (pintype "passive"))
      (node (ref "C31") (pin "2") (pinfunction "2_2") (pintype "passive"))
      (node (ref "C32") (pin "P$2") (pinfunction "2_P$2") (pintype "passive"))
      (node (ref "C33") (pin "P$2") (pinfunction "2_P$2") (pintype "passive"))
      (node (ref "C34") (pin "P$1") (pinfunction "1_P$1") (pintype "passive"))
      (node (ref "C35") (pin "P$1") (pinfunction "1_P$1") (pintype "passive"))
      (node (ref "C36") (pin "P$2") (pinfunction "2_P$2") (pintype "passive"))
      (node (ref "C37") (pin "P$2") (pinfunction "2_P$2") (pintype "passive"))
      (node (ref "C38") (pin "P$1") (pinfunction "1_P$1") (pintype "passive"))
      (node (ref "C39") (pin "P$2") (pinfunction "2_P$2") (pintype "passive"))
      (node (ref "C4") (pin "P$2") (pinfunction "2_P$2") (pintype "passive"))
      (node (ref "C40") (pin "P$2") (pinfunction "2_P$2") (pintype "passive"))
      (node (ref "C41") (pin "P$2") (pinfunction "2_P$2") (pintype "passive"))
      (node (ref "C42") (pin "P$2") (pinfunction "2_P$2") (pintype "passive"))
      (node (ref "C43") (pin "P$1") (pinfunction "1_P$1") (pintype "passive"))
      (node (ref "C5") (pin "P$2") (pinfunction "2_P$2") (pintype "passive"))
      (node (ref "C6") (pin "P$2") (pinfunction "2_P$2") (pintype "passive"))
      (node (ref "C7") (pin "P$2") (pinfunction "2_P$2") (pintype "passive"))
      (node (ref "C8") (pin "P$2") (pinfunction "2_P$2") (pintype "passive"))
      (node (ref "C9") (pin "P$2") (pinfunction "2_P$2") (pintype "passive"))
      (node (ref "FID1") (pin "P$1") (pinfunction "P$1_P$1") (pintype "bidirectional"))
      (node (ref "FID2") (pin "P$1") (pinfunction "P$1_P$1") (pintype "bidirectional"))
      (node (ref "FID3") (pin "P$1") (pinfunction "P$1_P$1") (pintype "bidirectional"))
      (node (ref "FID4") (pin "P$1") (pinfunction "P$1_P$1") (pintype "bidirectional"))
      (node (ref "FID5") (pin "P$1") (pinfunction "P$1_P$1") (pintype "bidirectional"))
      (node (ref "FID6") (pin "P$1") (pinfunction "P$1_P$1") (pintype "bidirectional"))
      (node (ref "FID7") (pin "P$1") (pinfunction "P$1_P$1") (pintype "bidirectional"))
      (node (ref "J1") (pin "6") (pinfunction "SUPPLY_VOLTAGE_GROUND_6") (pintype "power_in"))
      (node (ref "J2") (pin "P$1") (pinfunction "P$1_P$1") (pintype "bidirectional"))
      (node (ref "J3") (pin "10") (pinfunction "10_10") (pintype "passive"))
      (node (ref "J3") (pin "6") (pinfunction "6_6") (pintype "passive"))
      (node (ref "J3") (pin "8") (pinfunction "8_8") (pintype "passive"))
      (node (ref "J6") (pin "GND") (pinfunction "GND_GND") (pintype "power_in"))
      (node (ref "J7") (pin "P$5") (pinfunction "GND_P$5") (pintype "bidirectional"))
      (node (ref "J8") (pin "P$1") (pinfunction "P$1_P$1") (pintype "bidirectional"))
      (node (ref "J9") (pin "10") (pinfunction "10_10") (pintype "passive"))
      (node (ref "J9") (pin "2") (pinfunction "2_2") (pintype "passive"))
      (node (ref "J9") (pin "4") (pinfunction "4_4") (pintype "passive"))
      (node (ref "J9") (pin "6") (pinfunction "6_6") (pintype "passive"))
      (node (ref "J9") (pin "8") (pinfunction "8_8") (pintype "passive"))
      (node (ref "LED1") (pin "2") (pinfunction "C_2") (pintype "passive"))
      (node (ref "R1") (pin "P$1") (pinfunction "1_P$1") (pintype "passive"))
      (node (ref "R21") (pin "P$1") (pinfunction "1_P$1") (pintype "passive"))
      (node (ref "R22") (pin "P$1") (pinfunction "1_P$1") (pintype "passive"))
      (node (ref "R23") (pin "P$1") (pinfunction "1_P$1") (pintype "passive"))
      (node (ref "R24") (pin "P$1") (pinfunction "1_P$1") (pintype "passive"))
      (node (ref "RJ1") (pin "10") (pinfunction "GLO_10") (pintype "bidirectional"))
      (node (ref "RJ1") (pin "8") (pinfunction "P8_8") (pintype "bidirectional"))
      (node (ref "U1") (pin "22") (pinfunction "GND_22") (pintype "power_in"))
      (node (ref "U1") (pin "25") (pinfunction "25_25") (pintype "passive"))
      (node (ref "U2") (pin "2") (pinfunction "GND_2") (pintype "input"))
      (node (ref "U3") (pin "111") (pinfunction "VSS(IO)5_111") (pintype "bidirectional"))
      (node (ref "U3") (pin "124") (pinfunction "VSS(IO)6_124") (pintype "bidirectional"))
      (node (ref "U3") (pin "139") (pinfunction "VSS(IO)7_139") (pintype "bidirectional"))
      (node (ref "U3") (pin "150") (pinfunction "VSS(IO)8_150") (pintype "bidirectional"))
      (node (ref "U3") (pin "153") (pinfunction "VREFL_153") (pintype "bidirectional"))
      (node (ref "U3") (pin "156") (pinfunction "AVSS0_156") (pintype "bidirectional"))
      (node (ref "U3") (pin "157") (pinfunction "VREFL0_157") (pintype "bidirectional"))
      (node (ref "U3") (pin "170") (pinfunction "VSS(IO)9_170") (pintype "bidirectional"))
      (node (ref "U3") (pin "22") (pinfunction "VSS1_22") (pintype "bidirectional"))
      (node (ref "U3") (pin "28") (pinfunction "AVSS_USBHS_28") (pintype "bidirectional"))
      (node (ref "U3") (pin "29") (pinfunction "PVSS_USBHS_29") (pintype "bidirectional"))
      (node (ref "U3") (pin "30") (pinfunction "VSS2_USBHS_30") (pintype "bidirectional"))
      (node (ref "U3") (pin "33") (pinfunction "VSS1_USBHS_33") (pintype "bidirectional"))
      (node (ref "U3") (pin "35") (pinfunction "VSSIO_35") (pintype "bidirectional"))
      (node (ref "U3") (pin "45") (pinfunction "VSS_USB_45") (pintype "bidirectional"))
      (node (ref "U3") (pin "60") (pinfunction "VSS(IO)2_60") (pintype "bidirectional"))
      (node (ref "U3") (pin "63") (pinfunction "VSS(IO/DCDC)_63") (pintype "bidirectional"))
      (node (ref "U3") (pin "66") (pinfunction "VCC_DCDC(IO/DCDC)_66") (pintype "bidirectional"))
      (node (ref "U3") (pin "83") (pinfunction "VSS(IO)3_83") (pintype "bidirectional"))
      (node (ref "U3") (pin "98") (pinfunction "VSS(IO)4_98") (pintype "bidirectional"))
      (node (ref "X1") (pin "2") (pinfunction "2_2") (pintype "bidirectional"))
      (node (ref "X1") (pin "4") (pinfunction "4_4") (pintype "bidirectional"))
      (node (ref "X2") (pin "2") (pinfunction "2_2") (pintype "bidirectional"))
      (node (ref "X2") (pin "4") (pinfunction "4_4") (pintype "bidirectional"))
    )
    (net (code "17") (name "GNDE") (class "Default")
      (node (ref "J1") (pin "S1") (pinfunction "SHIELD_S1") (pintype "passive"))
      (node (ref "J1") (pin "S2") (pinfunction "SHIELD_S2") (pintype "passive"))
      (node (ref "J1") (pin "S3") (pinfunction "SHIELD_S3") (pintype "passive"))
      (node (ref "J1") (pin "S4") (pinfunction "SHIELD_S4") (pintype "passive"))
      (node (ref "J2") (pin "P$4") (pinfunction "P$4_P$4") (pintype "bidirectional"))
      (node (ref "J6") (pin "SHLD1") (pinfunction "SHIELD_1_SHLD1") (pintype "bidirectional"))
      (node (ref "J6") (pin "SHLD2") (pinfunction "SHIELD_2_SHLD2") (pintype "bidirectional"))
      (node (ref "J7") (pin "P$6") (pinfunction "SHIELD1_P$6") (pintype "bidirectional"))
      (node (ref "J7") (pin "P$7") (pinfunction "SHIELD2_P$7") (pintype "bidirectional"))
      (node (ref "J7") (pin "P$8") (pinfunction "SHIELD3_P$8") (pintype "bidirectional"))
      (node (ref "J7") (pin "P$9") (pinfunction "SHIELD4_P$9") (pintype "bidirectional"))
      (node (ref "RJ1") (pin "13") (pinfunction "GNDE0_13") (pintype "bidirectional"))
      (node (ref "RJ1") (pin "14") (pinfunction "GNDE1_14") (pintype "bidirectional"))
    )
    (net (code "18") (name "ID") (class "Default")
      (node (ref "J7") (pin "P$4") (pinfunction "ID_P$4") (pintype "bidirectional"))
    )
    (net (code "19") (name "IIC_1_SCL") (class "Default")
      (node (ref "J8") (pin "P$5") (pinfunction "P$5_P$5") (pintype "bidirectional"))
      (node (ref "R14") (pin "P$2") (pinfunction "2_P$2") (pintype "passive"))
      (node (ref "U3") (pin "132") (pinfunction "P1_0_132") (pintype "bidirectional"))
    )
    (net (code "20") (name "IIC_1_SDA") (class "Default")
      (node (ref "J8") (pin "P$6") (pinfunction "P$6_P$6") (pintype "bidirectional"))
      (node (ref "R15") (pin "P$2") (pinfunction "2_P$2") (pintype "passive"))
      (node (ref "U3") (pin "131") (pinfunction "P1_1_131") (pintype "bidirectional"))
    )
    (net (code "21") (name "INT_MI_01") (class "Default")
      (node (ref "J8") (pin "P$39") (pinfunction "P$39_P$39") (pintype "bidirectional"))
      (node (ref "U3") (pin "87") (pinfunction "P3_1_87") (pintype "bidirectional"))
    )
    (net (code "22") (name "INT_MI_02") (class "Default")
      (node (ref "J8") (pin "P$40") (pinfunction "P$40_P$40") (pintype "bidirectional"))
      (node (ref "U3") (pin "86") (pinfunction "P3_2_86") (pintype "bidirectional"))
    )
    (net (code "23") (name "INT_MI_03") (class "Default")
      (node (ref "J8") (pin "P$9") (pinfunction "P$9_P$9") (pintype "bidirectional"))
      (node (ref "U3") (pin "128") (pinfunction "P1_4_128") (pintype "bidirectional"))
    )
    (net (code "24") (name "INT_MI_04") (class "Default")
      (node (ref "J8") (pin "P$10") (pinfunction "P$10_P$10") (pintype "bidirectional"))
      (node (ref "U3") (pin "127") (pinfunction "P1_5_127") (pintype "bidirectional"))
    )
    (net (code "25") (name "LED1{slash}SPEED") (class "Default")
      (node (ref "RJ1") (pin "11") (pinfunction "YLO_11") (pintype "bidirectional"))
      (node (ref "U1") (pin "23") (pinfunction "LED0/ANEN_SPEED_23") (pintype "bidirectional"))
    )
    (net (code "26") (name "NC") (class "Default")
      (node (ref "RJ1") (pin "7") (pinfunction "P7_7") (pintype "bidirectional"))
    )
    (net (code "27") (name "Net-(C8-1)") (class "Default")
      (node (ref "C8") (pin "P$1") (pinfunction "1_P$1") (pintype "passive"))
      (node (ref "C9") (pin "P$1") (pinfunction "1_P$1") (pintype "passive"))
      (node (ref "FB1") (pin "2") (pinfunction "P$2_2") (pintype "bidirectional"))
      (node (ref "U1") (pin "2") (pinfunction "VDDA_3.3_2") (pintype "power_in"))
    )
    (net (code "28") (name "Net-(C24-2)") (class "Default")
      (node (ref "C24") (pin "P$2") (pinfunction "2_P$2") (pintype "passive"))
      (node (ref "U3") (pin "148") (pinfunction "VCL2_148") (pintype "bidirectional"))
    )
    (net (code "29") (name "Net-(C28-1)") (class "Default")
      (node (ref "C28") (pin "P$1") (pinfunction "1_P$1") (pintype "passive"))
      (node (ref "J7") (pin "P$1") (pinfunction "VBUS_P$1") (pintype "bidirectional"))
      (node (ref "R16") (pin "P$2") (pinfunction "2_P$2") (pintype "passive"))
      (node (ref "R21") (pin "P$2") (pinfunction "2_P$2") (pintype "passive"))
    )
    (net (code "30") (name "Net-(C33-1)") (class "Default")
      (node (ref "C33") (pin "P$1") (pinfunction "1_P$1") (pintype "passive"))
      (node (ref "U3") (pin "19") (pinfunction "VCLO_19") (pintype "bidirectional"))
    )
    (net (code "31") (name "Net-(C42-1)") (class "Default")
      (node (ref "C42") (pin "P$1") (pinfunction "1_P$1") (pintype "passive"))
      (node (ref "U3") (pin "62") (pinfunction "VCL1_62") (pintype "bidirectional"))
    )
    (net (code "32") (name "Net-(J7-D+)") (class "Default")
      (node (ref "J7") (pin "P$3") (pinfunction "D+_P$3") (pintype "bidirectional"))
      (node (ref "R18") (pin "P$2") (pinfunction "2_P$2") (pintype "passive"))
    )
    (net (code "33") (name "Net-(J7-D-)") (class "Default")
      (node (ref "J7") (pin "P$2") (pinfunction "D-_P$2") (pintype "bidirectional"))
      (node (ref "R17") (pin "P$2") (pinfunction "2_P$2") (pintype "passive"))
    )
    (net (code "34") (name "Net-(LED1-A)") (class "Default")
      (node (ref "LED1") (pin "1") (pinfunction "A_1") (pintype "passive"))
      (node (ref "R5") (pin "P$1") (pinfunction "1_P$1") (pintype "passive"))
    )
    (net (code "35") (name "Net-(R22-2)") (class "Default")
      (node (ref "R22") (pin "P$2") (pinfunction "2_P$2") (pintype "passive"))
      (node (ref "U3") (pin "27") (pinfunction "USBHS_RREF_27") (pintype "bidirectional"))
    )
    (net (code "36") (name "Net-(R23-2)") (class "Default")
      (node (ref "R23") (pin "P$2") (pinfunction "2_P$2") (pintype "passive"))
      (node (ref "U3") (pin "64") (pinfunction "VLO1(DCDC)_64") (pintype "bidirectional"))
    )
    (net (code "37") (name "Net-(R24-2)") (class "Default")
      (node (ref "R24") (pin "P$2") (pinfunction "2_P$2") (pintype "passive"))
      (node (ref "U3") (pin "65") (pinfunction "VLO2(DCDC)_65") (pintype "bidirectional"))
    )
    (net (code "38") (name "P0_00") (class "Default")
      (node (ref "J4") (pin "P$2") (pinfunction "P$2_P$2") (pintype "bidirectional"))
      (node (ref "U3") (pin "169") (pinfunction "P0_0/AN0\\00_169") (pintype "bidirectional"))
    )
    (net (code "39") (name "P0_01") (class "Default")
      (node (ref "J4") (pin "P$1") (pinfunction "P$1_P$1") (pintype "bidirectional"))
      (node (ref "U3") (pin "168") (pinfunction "P0_1/AN001_168") (pintype "bidirectional"))
    )
    (net (code "40") (name "P0_02") (class "Default")
      (node (ref "J5") (pin "1") (pinfunction "1_1") (pintype "passive"))
      (node (ref "U3") (pin "167") (pinfunction "P0_2/AN002_167") (pintype "bidirectional"))
    )
    (net (code "41") (name "P0_03") (class "Default")
      (node (ref "J5") (pin "3") (pinfunction "3_3") (pintype "passive"))
      (node (ref "U3") (pin "166") (pinfunction "P0_3/PGAVSS000_166") (pintype "bidirectional"))
    )
    (net (code "42") (name "P0_04") (class "Default")
      (node (ref "J5") (pin "5") (pinfunction "5_5") (pintype "passive"))
      (node (ref "U3") (pin "165") (pinfunction "P0_4/AN100_165") (pintype "bidirectional"))
    )
    (net (code "43") (name "P0_05") (class "Default")
      (node (ref "J5") (pin "7") (pinfunction "7_7") (pintype "passive"))
      (node (ref "U3") (pin "164") (pinfunction "P0_5/AN101_164") (pintype "bidirectional"))
    )
    (net (code "44") (name "P0_06") (class "Default")
      (node (ref "J5") (pin "9") (pinfunction "9_9") (pintype "passive"))
      (node (ref "U3") (pin "163") (pinfunction "P0_6/AN102_163") (pintype "bidirectional"))
    )
    (net (code "45") (name "P0_07") (class "Default")
      (node (ref "J5") (pin "10") (pinfunction "10_10") (pintype "passive"))
      (node (ref "U3") (pin "162") (pinfunction "P0_7/PGVSS100_162") (pintype "bidirectional"))
    )
    (net (code "46") (name "P0_08") (class "Default")
      (node (ref "J5") (pin "8") (pinfunction "8_8") (pintype "passive"))
      (node (ref "U3") (pin "161") (pinfunction "P0_8/AN003_161") (pintype "bidirectional"))
    )
    (net (code "47") (name "P0_09") (class "Default")
      (node (ref "J5") (pin "6") (pinfunction "6_6") (pintype "passive"))
      (node (ref "U3") (pin "160") (pinfunction "P0_9/AN004_160") (pintype "bidirectional"))
    )
    (net (code "48") (name "P0_14") (class "Default")
      (node (ref "J5") (pin "4") (pinfunction "4_4") (pintype "passive"))
      (node (ref "U3") (pin "152") (pinfunction "P0_14/DA0/AN005/AN105_152") (pintype "bidirectional"))
    )
    (net (code "49") (name "P0_15") (class "Default")
      (node (ref "J5") (pin "2") (pinfunction "2_2") (pintype "passive"))
      (node (ref "U3") (pin "151") (pinfunction "P0_15/DA1/AN006/AN106_151") (pintype "bidirectional"))
    )
    (net (code "50") (name "P1_02") (class "Default")
      (node (ref "J8") (pin "P$7") (pinfunction "P$7_P$7") (pintype "bidirectional"))
      (node (ref "U3") (pin "130") (pinfunction "P1_2_130") (pintype "bidirectional"))
    )
    (net (code "51") (name "P1_03") (class "Default")
      (node (ref "J8") (pin "P$8") (pinfunction "P$8_P$8") (pintype "bidirectional"))
      (node (ref "U3") (pin "129") (pinfunction "P1_3_129") (pintype "bidirectional"))
    )
    (net (code "52") (name "P1_06") (class "Default")
      (node (ref "J8") (pin "P$11") (pinfunction "P$11_P$11") (pintype "bidirectional"))
      (node (ref "U3") (pin "126") (pinfunction "P1_6_126") (pintype "bidirectional"))
    )
    (net (code "53") (name "P1_07") (class "Default")
      (node (ref "J8") (pin "P$12") (pinfunction "P$12_P$12") (pintype "bidirectional"))
      (node (ref "U3") (pin "125") (pinfunction "P1_7_125") (pintype "bidirectional"))
    )
    (net (code "54") (name "P1_11") (class "Default")
      (node (ref "J8") (pin "P$38") (pinfunction "P$38_P$38") (pintype "bidirectional"))
      (node (ref "U3") (pin "92") (pinfunction "P1_11_92") (pintype "bidirectional"))
    )
    (net (code "55") (name "P1_12") (class "Default")
      (node (ref "J8") (pin "P$37") (pinfunction "P$37_P$37") (pintype "bidirectional"))
      (node (ref "U3") (pin "93") (pinfunction "P1_12_93") (pintype "bidirectional"))
    )
    (net (code "56") (name "P1_13") (class "Default")
      (node (ref "J8") (pin "P$36") (pinfunction "P$36_P$36") (pintype "bidirectional"))
      (node (ref "U3") (pin "94") (pinfunction "P1_13_94") (pintype "bidirectional"))
    )
    (net (code "57") (name "P1_14") (class "Default")
      (node (ref "J8") (pin "P$35") (pinfunction "P$35_P$35") (pintype "bidirectional"))
      (node (ref "U3") (pin "95") (pinfunction "P1_14_95") (pintype "bidirectional"))
    )
    (net (code "58") (name "P1_15") (class "Default")
      (node (ref "J8") (pin "P$34") (pinfunction "P$34_P$34") (pintype "bidirectional"))
      (node (ref "U3") (pin "96") (pinfunction "P1_15_96") (pintype "bidirectional"))
    )
    (net (code "59") (name "P2_00") (class "Default")
      (node (ref "J10") (pin "P$13") (pinfunction "P$13_P$13") (pintype "bidirectional"))
      (node (ref "U3") (pin "69") (pinfunction "P2_0(INPUT_ONLY)_69") (pintype "bidirectional"))
    )
    (net (code "60") (name "P2_01") (class "Default")
      (node (ref "J10") (pin "P$14") (pinfunction "P$14_P$14") (pintype "bidirectional"))
      (node (ref "U3") (pin "68") (pinfunction "P2_1/MD_68") (pintype "bidirectional"))
    )
    (net (code "61") (name "P2_02") (class "Default")
      (node (ref "J10") (pin "P$19") (pinfunction "P$19_P$19") (pintype "bidirectional"))
      (node (ref "U3") (pin "54") (pinfunction "P2_2_54") (pintype "bidirectional"))
    )
    (net (code "62") (name "P2_03") (class "Default")
      (node (ref "J9") (pin "1") (pinfunction "1_1") (pintype "passive"))
      (node (ref "U3") (pin "53") (pinfunction "P2_3_53") (pintype "bidirectional"))
    )
    (net (code "63") (name "P2_04") (class "Default")
      (node (ref "J9") (pin "3") (pinfunction "3_3") (pintype "passive"))
      (node (ref "U3") (pin "52") (pinfunction "P2_4_52") (pintype "bidirectional"))
    )
    (net (code "64") (name "P2_05") (class "Default")
      (node (ref "J9") (pin "5") (pinfunction "5_5") (pintype "passive"))
      (node (ref "U3") (pin "51") (pinfunction "P2_5_51") (pintype "bidirectional"))
    )
    (net (code "65") (name "P2_06") (class "Default")
      (node (ref "J9") (pin "7") (pinfunction "7_7") (pintype "passive"))
      (node (ref "U3") (pin "50") (pinfunction "P2_6_50") (pintype "bidirectional"))
    )
    (net (code "66") (name "P2_07") (class "Default")
      (node (ref "J9") (pin "9") (pinfunction "9_9") (pintype "passive"))
      (node (ref "U3") (pin "49") (pinfunction "P2_7_49") (pintype "bidirectional"))
    )
    (net (code "67") (name "P3_03") (class "Default")
      (node (ref "J10") (pin "P$2") (pinfunction "P$2_P$2") (pintype "bidirectional"))
      (node (ref "U3") (pin "85") (pinfunction "P3_3_85") (pintype "bidirectional"))
    )
    (net (code "68") (name "P3_04") (class "Default")
      (node (ref "J10") (pin "P$4") (pinfunction "P$4_P$4") (pintype "bidirectional"))
      (node (ref "U3") (pin "82") (pinfunction "P3_4_82") (pintype "bidirectional"))
    )
    (net (code "69") (name "P3_05") (class "Default")
      (node (ref "J10") (pin "P$6") (pinfunction "P$6_P$6") (pintype "bidirectional"))
      (node (ref "U3") (pin "81") (pinfunction "P3_5_81") (pintype "bidirectional"))
    )
    (net (code "70") (name "P3_06") (class "Default")
      (node (ref "J10") (pin "P$1") (pinfunction "P$1_P$1") (pintype "bidirectional"))
      (node (ref "U3") (pin "80") (pinfunction "P3_6_80") (pintype "bidirectional"))
    )
    (net (code "71") (name "P3_07") (class "Default")
      (node (ref "J10") (pin "P$3") (pinfunction "P$3_P$3") (pintype "bidirectional"))
      (node (ref "U3") (pin "79") (pinfunction "P3_7_79") (pintype "bidirectional"))
    )
    (net (code "72") (name "P3_09") (class "Default")
      (node (ref "J10") (pin "P$5") (pinfunction "P$5_P$5") (pintype "bidirectional"))
      (node (ref "U3") (pin "77") (pinfunction "P3_9_77") (pintype "bidirectional"))
    )
    (net (code "73") (name "P3_10") (class "Default")
      (node (ref "J10") (pin "P$7") (pinfunction "P$7_P$7") (pintype "bidirectional"))
      (node (ref "U3") (pin "76") (pinfunction "P3_10_76") (pintype "bidirectional"))
    )
    (net (code "74") (name "P3_11") (class "Default")
      (node (ref "J10") (pin "P$8") (pinfunction "P$8_P$8") (pintype "bidirectional"))
      (node (ref "U3") (pin "75") (pinfunction "P3_11_75") (pintype "bidirectional"))
    )
    (net (code "75") (name "P3_12") (class "Default")
      (node (ref "J10") (pin "P$9") (pinfunction "P$9_P$9") (pintype "bidirectional"))
      (node (ref "U3") (pin "74") (pinfunction "P3_12_74") (pintype "bidirectional"))
    )
    (net (code "76") (name "P3_13") (class "Default")
      (node (ref "J10") (pin "P$20") (pinfunction "P$20_P$20") (pintype "bidirectional"))
      (node (ref "U3") (pin "55") (pinfunction "P3_13_55") (pintype "bidirectional"))
    )
    (net (code "77") (name "P3_14") (class "Default")
      (node (ref "J10") (pin "P$17") (pinfunction "P$17_P$17") (pintype "bidirectional"))
      (node (ref "U3") (pin "56") (pinfunction "P3_14_56") (pintype "bidirectional"))
    )
    (net (code "78") (name "P3_15") (class "Default")
      (node (ref "J10") (pin "P$18") (pinfunction "P$18_P$18") (pintype "bidirectional"))
      (node (ref "U3") (pin "57") (pinfunction "P3_15_57") (pintype "bidirectional"))
    )
    (net (code "79") (name "P4_00") (class "Default")
      (node (ref "J4") (pin "P$7") (pinfunction "P$7_P$7") (pintype "bidirectional"))
      (node (ref "U3") (pin "1") (pinfunction "P4_0_1") (pintype "bidirectional"))
    )
    (net (code "80") (name "P4_01") (class "Default")
      (node (ref "J4") (pin "P$8") (pinfunction "P$8_P$8") (pintype "bidirectional"))
      (node (ref "U3") (pin "2") (pinfunction "P4_1_2") (pintype "bidirectional"))
    )
    (net (code "81") (name "P4_02") (class "Default")
      (node (ref "J4") (pin "P$9") (pinfunction "P$9_P$9") (pintype "bidirectional"))
      (node (ref "U3") (pin "3") (pinfunction "P4_2_3") (pintype "bidirectional"))
    )
    (net (code "82") (name "P4_08") (class "Default")
      (node (ref "J4") (pin "P$20") (pinfunction "P$20_P$20") (pintype "bidirectional"))
      (node (ref "U3") (pin "43") (pinfunction "P4_8_43") (pintype "bidirectional"))
    )
    (net (code "83") (name "P4_09") (class "Default")
      (node (ref "J4") (pin "P$19") (pinfunction "P$19_P$19") (pintype "bidirectional"))
      (node (ref "U3") (pin "42") (pinfunction "P4_9_42") (pintype "bidirectional"))
    )
    (net (code "84") (name "P4_10") (class "Default")
      (node (ref "J4") (pin "P$18") (pinfunction "P$18_P$18") (pintype "bidirectional"))
      (node (ref "U3") (pin "41") (pinfunction "P4_10_41") (pintype "bidirectional"))
    )
    (net (code "85") (name "P4_11") (class "Default")
      (node (ref "J4") (pin "P$17") (pinfunction "P$17_P$17") (pintype "bidirectional"))
      (node (ref "U3") (pin "40") (pinfunction "P4_11_40") (pintype "bidirectional"))
    )
    (net (code "86") (name "P4_12") (class "Default")
      (node (ref "J4") (pin "P$16") (pinfunction "P$16_P$16") (pintype "bidirectional"))
      (node (ref "U3") (pin "39") (pinfunction "P4_12_39") (pintype "bidirectional"))
    )
    (net (code "87") (name "P4_13") (class "Default")
      (node (ref "J4") (pin "P$15") (pinfunction "P$15_P$15") (pintype "bidirectional"))
      (node (ref "U3") (pin "38") (pinfunction "P4_13_38") (pintype "bidirectional"))
    )
    (net (code "88") (name "P4_14") (class "Default")
      (node (ref "J4") (pin "P$14") (pinfunction "P$14_P$14") (pintype "bidirectional"))
      (node (ref "U3") (pin "37") (pinfunction "P4_14_37") (pintype "bidirectional"))
    )
    (net (code "89") (name "P4_15") (class "Default")
      (node (ref "J4") (pin "P$13") (pinfunction "P$13_P$13") (pintype "bidirectional"))
      (node (ref "U3") (pin "36") (pinfunction "P4_15_36") (pintype "bidirectional"))
    )
    (net (code "90") (name "P5_11") (class "Default")
      (node (ref "J4") (pin "P$6") (pinfunction "P$6_P$6") (pintype "bidirectional"))
      (node (ref "U3") (pin "176") (pinfunction "P5_11_176") (pintype "bidirectional"))
    )
    (net (code "91") (name "P5_12") (class "Default")
      (node (ref "J4") (pin "P$5") (pinfunction "P$5_P$5") (pintype "bidirectional"))
      (node (ref "U3") (pin "175") (pinfunction "P5_12_175") (pintype "bidirectional"))
    )
    (net (code "92") (name "P5_13") (class "Default")
      (node (ref "J4") (pin "P$4") (pinfunction "P$4_P$4") (pintype "bidirectional"))
      (node (ref "U3") (pin "174") (pinfunction "P5_13_174") (pintype "bidirectional"))
    )
    (net (code "93") (name "P6_00") (class "Default")
      (node (ref "J8") (pin "P$13") (pinfunction "P$13_P$13") (pintype "bidirectional"))
      (node (ref "U3") (pin "122") (pinfunction "P6_0_122") (pintype "bidirectional"))
    )
    (net (code "94") (name "P6_01") (class "Default")
      (node (ref "J8") (pin "P$14") (pinfunction "P$14_P$14") (pintype "bidirectional"))
      (node (ref "U3") (pin "121") (pinfunction "P6_1_121") (pintype "bidirectional"))
    )
    (net (code "95") (name "P6_02") (class "Default")
      (node (ref "J8") (pin "P$15") (pinfunction "P$15_P$15") (pintype "bidirectional"))
      (node (ref "U3") (pin "120") (pinfunction "P6_2_120") (pintype "bidirectional"))
    )
    (net (code "96") (name "P6_03") (class "Default")
      (node (ref "J8") (pin "P$16") (pinfunction "P$16_P$16") (pintype "bidirectional"))
      (node (ref "U3") (pin "119") (pinfunction "P6_3_119") (pintype "bidirectional"))
    )
    (net (code "97") (name "P6_04") (class "Default")
      (node (ref "J8") (pin "P$17") (pinfunction "P$17_P$17") (pintype "bidirectional"))
      (node (ref "U3") (pin "118") (pinfunction "P6_4_118") (pintype "bidirectional"))
    )
    (net (code "98") (name "P6_05") (class "Default")
      (node (ref "J8") (pin "P$18") (pinfunction "P$18_P$18") (pintype "bidirectional"))
      (node (ref "U3") (pin "117") (pinfunction "P6_5_117") (pintype "bidirectional"))
    )
    (net (code "99") (name "P6_06") (class "Default")
      (node (ref "J8") (pin "P$19") (pinfunction "P$19_P$19") (pintype "bidirectional"))
      (node (ref "U3") (pin "116") (pinfunction "P6_6_116") (pintype "bidirectional"))
    )
    (net (code "100") (name "P6_07") (class "Default")
      (node (ref "J8") (pin "P$20") (pinfunction "P$20_P$20") (pintype "bidirectional"))
      (node (ref "U3") (pin "115") (pinfunction "P6_7_115") (pintype "bidirectional"))
    )
    (net (code "101") (name "P6_08") (class "Default")
      (node (ref "J8") (pin "P$33") (pinfunction "P$33_P$33") (pintype "bidirectional"))
      (node (ref "U3") (pin "99") (pinfunction "P6_8_99") (pintype "bidirectional"))
    )
    (net (code "102") (name "P6_09") (class "Default")
      (node (ref "J8") (pin "P$32") (pinfunction "P$32_P$32") (pintype "bidirectional"))
      (node (ref "U3") (pin "100") (pinfunction "P6_9_100") (pintype "bidirectional"))
    )
    (net (code "103") (name "P6_10") (class "Default")
      (node (ref "J8") (pin "P$31") (pinfunction "P$31_P$31") (pintype "bidirectional"))
      (node (ref "U3") (pin "101") (pinfunction "P6_10_101") (pintype "bidirectional"))
    )
    (net (code "104") (name "P6_11") (class "Default")
      (node (ref "J8") (pin "P$30") (pinfunction "P$30_P$30") (pintype "bidirectional"))
      (node (ref "U3") (pin "102") (pinfunction "P6_11_102") (pintype "bidirectional"))
    )
    (net (code "105") (name "P6_12") (class "Default")
      (node (ref "J8") (pin "P$29") (pinfunction "P$29_P$29") (pintype "bidirectional"))
      (node (ref "U3") (pin "103") (pinfunction "P6_12_103") (pintype "bidirectional"))
    )
    (net (code "106") (name "P6_13") (class "Default")
      (node (ref "J8") (pin "P$28") (pinfunction "P$28_P$28") (pintype "bidirectional"))
      (node (ref "U3") (pin "104") (pinfunction "P6_13_104") (pintype "bidirectional"))
    )
    (net (code "107") (name "P6_14") (class "Default")
      (node (ref "J8") (pin "P$27") (pinfunction "P$27_P$27") (pintype "bidirectional"))
      (node (ref "U3") (pin "105") (pinfunction "P6_14_105") (pintype "bidirectional"))
    )
    (net (code "108") (name "P6_15") (class "Default")
      (node (ref "J8") (pin "P$26") (pinfunction "P$26_P$26") (pintype "bidirectional"))
      (node (ref "U3") (pin "106") (pinfunction "P6_15_106") (pintype "bidirectional"))
    )
    (net (code "109") (name "P7_06") (class "Default")
      (node (ref "J4") (pin "P$10") (pinfunction "P$10_P$10") (pintype "bidirectional"))
      (node (ref "U3") (pin "14") (pinfunction "P7_6_14") (pintype "bidirectional"))
    )
    (net (code "110") (name "P7_07") (class "Default")
      (node (ref "J4") (pin "P$11") (pinfunction "P$11_P$11") (pintype "bidirectional"))
      (node (ref "U3") (pin "15") (pinfunction "P7_7_15") (pintype "bidirectional"))
    )
    (net (code "111") (name "P8_00") (class "Default")
      (node (ref "J8") (pin "P$4") (pinfunction "P$4_P$4") (pintype "bidirectional"))
      (node (ref "U3") (pin "133") (pinfunction "P8_0_133") (pintype "bidirectional"))
    )
    (net (code "112") (name "P8_01") (class "Default")
      (node (ref "J8") (pin "P$3") (pinfunction "P$3_P$3") (pintype "bidirectional"))
      (node (ref "U3") (pin "134") (pinfunction "P8_1_134") (pintype "bidirectional"))
    )
    (net (code "113") (name "P8_02") (class "Default")
      (node (ref "J8") (pin "P$2") (pinfunction "P$2_P$2") (pintype "bidirectional"))
      (node (ref "U3") (pin "135") (pinfunction "P8_2_135") (pintype "bidirectional"))
    )
    (net (code "114") (name "P8_03") (class "Default")
      (node (ref "U3") (pin "136") (pinfunction "P8_3_136") (pintype "bidirectional"))
    )
    (net (code "115") (name "P8_04") (class "Default")
      (node (ref "U3") (pin "137") (pinfunction "P8_4_137") (pintype "bidirectional"))
    )
    (net (code "116") (name "P8_05") (class "Default")
      (node (ref "J4") (pin "P$3") (pinfunction "P$3_P$3") (pintype "bidirectional"))
      (node (ref "U3") (pin "173") (pinfunction "P8_5_173") (pintype "bidirectional"))
    )
    (net (code "117") (name "P9_00") (class "Default")
      (node (ref "J10") (pin "P$16") (pinfunction "P$16_P$16") (pintype "bidirectional"))
      (node (ref "U3") (pin "58") (pinfunction "P9_0_58") (pintype "bidirectional"))
    )
    (net (code "118") (name "P9_01") (class "Default")
      (node (ref "J10") (pin "P$15") (pinfunction "P$15_P$15") (pintype "bidirectional"))
      (node (ref "U3") (pin "59") (pinfunction "P9_1_59") (pintype "bidirectional"))
    )
    (net (code "119") (name "P9_05") (class "Default")
      (node (ref "J10") (pin "P$10") (pinfunction "P$10_P$10") (pintype "bidirectional"))
      (node (ref "U3") (pin "73") (pinfunction "P9_5_73") (pintype "bidirectional"))
    )
    (net (code "120") (name "P9_06") (class "Default")
      (node (ref "J10") (pin "P$11") (pinfunction "P$11_P$11") (pintype "bidirectional"))
      (node (ref "U3") (pin "72") (pinfunction "P9_6_72") (pintype "bidirectional"))
    )
    (net (code "121") (name "P9_07") (class "Default")
      (node (ref "J10") (pin "P$12") (pinfunction "P$12_P$12") (pintype "bidirectional"))
      (node (ref "U3") (pin "71") (pinfunction "P9_7_71") (pintype "bidirectional"))
    )
    (net (code "122") (name "P9_08") (class "Default")
      (node (ref "U3") (pin "70") (pinfunction "P9_8_70") (pintype "bidirectional"))
    )
    (net (code "123") (name "PA_00") (class "Default")
      (node (ref "J8") (pin "P$21") (pinfunction "P$21_P$21") (pintype "bidirectional"))
      (node (ref "U3") (pin "114") (pinfunction "PA_0_114") (pintype "bidirectional"))
    )
    (net (code "124") (name "PA_01") (class "Default")
      (node (ref "J8") (pin "P$22") (pinfunction "P$22_P$22") (pintype "bidirectional"))
      (node (ref "U3") (pin "113") (pinfunction "PA_1_113") (pintype "bidirectional"))
    )
    (net (code "125") (name "PA_08") (class "Default")
      (node (ref "J8") (pin "P$25") (pinfunction "P$25_P$25") (pintype "bidirectional"))
      (node (ref "U3") (pin "107") (pinfunction "PA_8_107") (pintype "bidirectional"))
    )
    (net (code "126") (name "PA_09") (class "Default")
      (node (ref "J8") (pin "P$24") (pinfunction "P$24_P$24") (pintype "bidirectional"))
      (node (ref "U3") (pin "108") (pinfunction "PA_9_108") (pintype "bidirectional"))
    )
    (net (code "127") (name "PA_10") (class "Default")
      (node (ref "J8") (pin "P$23") (pinfunction "P$23_P$23") (pintype "bidirectional"))
      (node (ref "U3") (pin "109") (pinfunction "PA_10_109") (pintype "bidirectional"))
    )
    (net (code "128") (name "PB_00") (class "Default")
      (node (ref "J4") (pin "P$12") (pinfunction "P$12_P$12") (pintype "bidirectional"))
      (node (ref "U3") (pin "16") (pinfunction "PB_0_16") (pintype "bidirectional"))
    )
    (net (code "129") (name "R51") (class "Default")
      (node (ref "R7") (pin "P$1") (pinfunction "1_P$1") (pintype "passive"))
      (node (ref "RJ1") (pin "12") (pinfunction "YHI_12") (pintype "bidirectional"))
    )
    (net (code "130") (name "R52") (class "Default")
      (node (ref "R8") (pin "P$1") (pinfunction "1_P$1") (pintype "passive"))
      (node (ref "RJ1") (pin "9") (pinfunction "GHI_9") (pintype "bidirectional"))
    )
    (net (code "131") (name "RESET") (class "Default")
      (node (ref "C16") (pin "P$1") (pinfunction "1_P$1") (pintype "passive"))
      (node (ref "J3") (pin "9") (pinfunction "9_9") (pintype "passive"))
      (node (ref "R13") (pin "P$1") (pinfunction "1_P$1") (pintype "passive"))
      (node (ref "U3") (pin "67") (pinfunction "RES#_67") (pintype "bidirectional"))
    )
    (net (code "132") (name "REXT") (class "Default")
      (node (ref "C3") (pin "P$1") (pinfunction "1_P$1") (pintype "passive"))
      (node (ref "R1") (pin "P$2") (pinfunction "2_P$2") (pintype "passive"))
      (node (ref "U1") (pin "9") (pinfunction "REXT_9") (pintype "input"))
    )
    (net (code "133") (name "RXD0") (class "Default")
      (node (ref "R10") (pin "P$2") (pinfunction "2_P$2") (pintype "passive"))
      (node (ref "U1") (pin "13") (pinfunction "RXD0_13") (pintype "bidirectional"))
    )
    (net (code "134") (name "RXD1") (class "Default")
      (node (ref "R9") (pin "P$2") (pinfunction "2_P$2") (pintype "passive"))
      (node (ref "U1") (pin "12") (pinfunction "RXD1_12") (pintype "bidirectional"))
    )
    (net (code "135") (name "RXER") (class "Default")
      (node (ref "R11") (pin "P$2") (pinfunction "2_P$2") (pintype "passive"))
      (node (ref "U1") (pin "17") (pinfunction "RXER_17") (pintype "bidirectional"))
    )
    (net (code "136") (name "RXM") (class "Default")
      (node (ref "RJ1") (pin "6") (pinfunction "RD-_6") (pintype "bidirectional"))
      (node (ref "U1") (pin "3") (pinfunction "RXM_3") (pintype "bidirectional"))
    )
    (net (code "137") (name "RXP") (class "Default")
      (node (ref "RJ1") (pin "3") (pinfunction "RD+_3") (pintype "bidirectional"))
      (node (ref "U1") (pin "4") (pinfunction "RXP_4") (pintype "bidirectional"))
    )
    (net (code "138") (name "SD1_CD") (class "Default")
      (node (ref "J1") (pin "10") (pinfunction "CD_SWITCH2_10") (pintype "bidirectional"))
      (node (ref "U3") (pin "146") (pinfunction "P5_6/AN019_146") (pintype "bidirectional"))
    )
    (net (code "139") (name "SD1_CLK") (class "Default")
      (node (ref "J1") (pin "5") (pinfunction "CLOCK_5") (pintype "bidirectional"))
      (node (ref "U3") (pin "140") (pinfunction "P5_0/AN016_140") (pintype "bidirectional"))
    )
    (net (code "140") (name "SD1_CMD") (class "Default")
      (node (ref "J1") (pin "3") (pinfunction "COMMAND/RESPONSE_3") (pintype "bidirectional"))
      (node (ref "U3") (pin "141") (pinfunction "P5_1/AN116_141") (pintype "bidirectional"))
    )
    (net (code "141") (name "SD1_DAT0") (class "Default")
      (node (ref "J1") (pin "7") (pinfunction "DATA_LINE[BIT_0]_7") (pintype "bidirectional"))
      (node (ref "U3") (pin "142") (pinfunction "P5_2/AN017_142") (pintype "bidirectional"))
    )
    (net (code "142") (name "SD1_DAT1") (class "Default")
      (node (ref "J1") (pin "8") (pinfunction "DATA_LINE[BIT_1]_8") (pintype "bidirectional"))
      (node (ref "U3") (pin "143") (pinfunction "P5_3/AN117_143") (pintype "bidirectional"))
    )
    (net (code "143") (name "SD1_DAT2") (class "Default")
      (node (ref "J1") (pin "1") (pinfunction "DATA_LINE[BIT_2]_1") (pintype "bidirectional"))
      (node (ref "U3") (pin "144") (pinfunction "P5_4/AN018_144") (pintype "bidirectional"))
    )
    (net (code "144") (name "SD1_DAT3") (class "Default")
      (node (ref "J1") (pin "2") (pinfunction "CARD_DETECT/DATA_LINE[BIT_3]_2") (pintype "bidirectional"))
      (node (ref "U3") (pin "145") (pinfunction "P5_5/AN118_145") (pintype "bidirectional"))
    )
    (net (code "145") (name "SD1_WP") (class "Default")
      (node (ref "J1") (pin "9") (pinfunction "CD_SWITCH1_9") (pintype "bidirectional"))
      (node (ref "U3") (pin "147") (pinfunction "P5_7/AN119_147") (pintype "bidirectional"))
    )
    (net (code "146") (name "TCK") (class "Default")
      (node (ref "J3") (pin "7") (pinfunction "7_7") (pintype "passive"))
      (node (ref "U3") (pin "88") (pinfunction "P3_0_88") (pintype "bidirectional"))
    )
    (net (code "147") (name "TDI") (class "Default")
      (node (ref "J3") (pin "1") (pinfunction "1_1") (pintype "passive"))
      (node (ref "U3") (pin "91") (pinfunction "P1_10_91") (pintype "bidirectional"))
    )
    (net (code "148") (name "TDO") (class "Default")
      (node (ref "J3") (pin "3") (pinfunction "3_3") (pintype "passive"))
      (node (ref "U3") (pin "90") (pinfunction "P1_9_90") (pintype "bidirectional"))
    )
    (net (code "149") (name "TMS") (class "Default")
      (node (ref "J3") (pin "5") (pinfunction "5_5") (pintype "passive"))
      (node (ref "U3") (pin "89") (pinfunction "P1_8_89") (pintype "bidirectional"))
    )
    (net (code "150") (name "TXM") (class "Default")
      (node (ref "RJ1") (pin "2") (pinfunction "TD-_2") (pintype "bidirectional"))
      (node (ref "U1") (pin "5") (pinfunction "TXM_5") (pintype "bidirectional"))
    )
    (net (code "151") (name "TXP") (class "Default")
      (node (ref "RJ1") (pin "1") (pinfunction "TD+_1") (pintype "bidirectional"))
      (node (ref "U1") (pin "6") (pinfunction "TXP_6") (pintype "bidirectional"))
    )
    (net (code "152") (name "USBHS_FAULT") (class "Default")
      (node (ref "R19") (pin "P$1") (pinfunction "1_P$1") (pintype "passive"))
      (node (ref "U2") (pin "3") (pinfunction "FLG_3") (pintype "input"))
      (node (ref "U3") (pin "78") (pinfunction "P3_8_78") (pintype "bidirectional"))
    )
    (net (code "153") (name "USBHS_N") (class "Default")
      (node (ref "J6") (pin "D-") (pinfunction "D-_D-") (pintype "bidirectional"))
      (node (ref "U3") (pin "31") (pinfunction "USBHS_DM_31") (pintype "bidirectional"))
    )
    (net (code "154") (name "USBHS_P") (class "Default")
      (node (ref "J6") (pin "D+") (pinfunction "D+_D+") (pintype "bidirectional"))
      (node (ref "U3") (pin "32") (pinfunction "USBHS_DP_32") (pintype "bidirectional"))
    )
    (net (code "155") (name "USBHS_VBUS") (class "Default")
      (node (ref "C29") (pin "P$1") (pinfunction "1_P$1") (pintype "passive"))
      (node (ref "C31") (pin "1") (pinfunction "1_1") (pintype "passive"))
      (node (ref "J6") (pin "VBUS") (pinfunction "VBUS_VBUS") (pintype "power_in"))
      (node (ref "U2") (pin "5") (pinfunction "OUT_5") (pintype "input"))
      (node (ref "U3") (pin "17") (pinfunction "PB_1_17") (pintype "bidirectional"))
    )
    (net (code "156") (name "USBHS_VBUSEN") (class "Default")
      (node (ref "R20") (pin "P$1") (pinfunction "1_P$1") (pintype "passive"))
      (node (ref "U2") (pin "1") (pinfunction "EN_1") (pintype "input"))
    )
    (net (code "157") (name "USB_N") (class "Default")
      (node (ref "R17") (pin "P$1") (pinfunction "1_P$1") (pintype "passive"))
      (node (ref "U3") (pin "46") (pinfunction "USB_DM_46") (pintype "bidirectional"))
    )
    (net (code "158") (name "USB_P") (class "Default")
      (node (ref "R18") (pin "P$1") (pinfunction "1_P$1") (pintype "passive"))
      (node (ref "U3") (pin "47") (pinfunction "USB_DP_47") (pintype "bidirectional"))
    )
    (net (code "159") (name "USB_VBUS_B") (class "Default")
      (node (ref "R16") (pin "P$1") (pinfunction "1_P$1") (pintype "passive"))
      (node (ref "U3") (pin "44") (pinfunction "P4_7_44") (pintype "bidirectional"))
    )
    (net (code "160") (name "VCL_F(FLASH)") (class "Default")
      (node (ref "C34") (pin "P$2") (pinfunction "2_P$2") (pintype "passive"))
      (node (ref "U3") (pin "112") (pinfunction "VCL_F(FLASH)_112") (pintype "bidirectional"))
    )
    (net (code "161") (name "VDD") (class "Default")
      (node (ref "C14") (pin "P$1") (pinfunction "1_P$1") (pintype "passive"))
      (node (ref "C15") (pin "P$1") (pinfunction "1_P$1") (pintype "passive"))
      (node (ref "C19") (pin "P$2") (pinfunction "2_P$2") (pintype "passive"))
      (node (ref "C20") (pin "P$2") (pinfunction "2_P$2") (pintype "passive"))
      (node (ref "C21") (pin "P$2") (pinfunction "2_P$2") (pintype "passive"))
      (node (ref "C22") (pin "P$2") (pinfunction "2_P$2") (pintype "passive"))
      (node (ref "C25") (pin "P$2") (pinfunction "2_P$2") (pintype "passive"))
      (node (ref "C27") (pin "P$2") (pinfunction "2_P$2") (pintype "passive"))
      (node (ref "C30") (pin "P$2") (pinfunction "2_P$2") (pintype "passive"))
      (node (ref "C35") (pin "P$2") (pinfunction "2_P$2") (pintype "passive"))
      (node (ref "C36") (pin "P$1") (pinfunction "1_P$1") (pintype "passive"))
      (node (ref "C38") (pin "P$2") (pinfunction "2_P$2") (pintype "passive"))
      (node (ref "C39") (pin "P$1") (pinfunction "1_P$1") (pintype "passive"))
      (node (ref "C4") (pin "P$1") (pinfunction "1_P$1") (pintype "passive"))
      (node (ref "C40") (pin "P$1") (pinfunction "1_P$1") (pintype "passive"))
      (node (ref "C41") (pin "P$1") (pinfunction "1_P$1") (pintype "passive"))
      (node (ref "C43") (pin "P$2") (pinfunction "2_P$2") (pintype "passive"))
      (node (ref "C5") (pin "P$1") (pinfunction "1_P$1") (pintype "passive"))
      (node (ref "C7") (pin "P$1") (pinfunction "1_P$1") (pintype "passive"))
      (node (ref "FB1") (pin "1") (pinfunction "P$1_1") (pintype "bidirectional"))
      (node (ref "J1") (pin "4") (pinfunction "SUPPLY_VOLTAGE_4") (pintype "power_in"))
      (node (ref "J3") (pin "2") (pinfunction "2_2") (pintype "passive"))
      (node (ref "J3") (pin "4") (pinfunction "4_4") (pintype "passive"))
      (node (ref "L1") (pin "2") (pinfunction "P$2_2") (pintype "bidirectional"))
      (node (ref "R13") (pin "P$2") (pinfunction "2_P$2") (pintype "passive"))
      (node (ref "R14") (pin "P$1") (pinfunction "1_P$1") (pintype "passive"))
      (node (ref "R15") (pin "P$1") (pinfunction "1_P$1") (pintype "passive"))
      (node (ref "R2") (pin "P$2") (pinfunction "2_P$2") (pintype "passive"))
      (node (ref "R3") (pin "P$2") (pinfunction "2_P$2") (pintype "passive"))
      (node (ref "R4") (pin "P$2") (pinfunction "2_P$2") (pintype "passive"))
      (node (ref "R5") (pin "P$2") (pinfunction "2_P$2") (pintype "passive"))
      (node (ref "R6") (pin "P$2") (pinfunction "2_P$2") (pintype "passive"))
      (node (ref "R7") (pin "P$2") (pinfunction "2_P$2") (pintype "passive"))
      (node (ref "R8") (pin "P$2") (pinfunction "2_P$2") (pintype "passive"))
      (node (ref "U1") (pin "14") (pinfunction "VDDIO_14") (pintype "power_in"))
      (node (ref "U3") (pin "110") (pinfunction "VCC(IO)5_110") (pintype "bidirectional"))
      (node (ref "U3") (pin "123") (pinfunction "VCC(IO)6_123") (pintype "bidirectional"))
      (node (ref "U3") (pin "138") (pinfunction "VCC(IO)7_138") (pintype "bidirectional"))
      (node (ref "U3") (pin "149") (pinfunction "VCC(IO)8_149") (pintype "bidirectional"))
      (node (ref "U3") (pin "154") (pinfunction "VREFH_154") (pintype "bidirectional"))
      (node (ref "U3") (pin "155") (pinfunction "AVCC0_155") (pintype "bidirectional"))
      (node (ref "U3") (pin "158") (pinfunction "VREFH0_158") (pintype "bidirectional"))
      (node (ref "U3") (pin "171") (pinfunction "VCC(IO)9_171") (pintype "bidirectional"))
      (node (ref "U3") (pin "25") (pinfunction "VCC1_25") (pintype "bidirectional"))
      (node (ref "U3") (pin "26") (pinfunction "AVCC_SUBHS_26") (pintype "bidirectional"))
      (node (ref "U3") (pin "34") (pinfunction "VCC_USBHS_34") (pintype "bidirectional"))
      (node (ref "U3") (pin "48") (pinfunction "VCC_USB_48") (pintype "bidirectional"))
      (node (ref "U3") (pin "61") (pinfunction "VCC(IO)2_61") (pintype "bidirectional"))
      (node (ref "U3") (pin "84") (pinfunction "VCC(IO)3_84") (pintype "bidirectional"))
      (node (ref "U3") (pin "97") (pinfunction "VCC(IO)4_97") (pintype "bidirectional"))
    )
    (net (code "162") (name "VDD5") (class "Default")
      (node (ref "C23") (pin "P$1") (pinfunction "1_P$1") (pintype "passive"))
      (node (ref "C26") (pin "P$1") (pinfunction "1_P$1") (pintype "passive"))
      (node (ref "J2") (pin "P$3") (pinfunction "P$3_P$3") (pintype "bidirectional"))
      (node (ref "R19") (pin "P$2") (pinfunction "2_P$2") (pintype "passive"))
      (node (ref "R20") (pin "P$2") (pinfunction "2_P$2") (pintype "passive"))
      (node (ref "U2") (pin "4") (pinfunction "VIN_4") (pintype "input"))
    )
    (net (code "163") (name "VDDIN") (class "Default")
      (node (ref "J2") (pin "P$2") (pinfunction "P$2_P$2") (pintype "bidirectional"))
      (node (ref "L1") (pin "1") (pinfunction "P$1_1") (pintype "bidirectional"))
    )
    (net (code "164") (name "VDD_1.2") (class "Default")
      (node (ref "C10") (pin "P$1") (pinfunction "1_P$1") (pintype "passive"))
      (node (ref "C11") (pin "P$1") (pinfunction "1_P$1") (pintype "passive"))
      (node (ref "U1") (pin "1") (pinfunction "VDD_1.2_1") (pintype "power_in"))
    )
    (net (code "165") (name "XCIN") (class "Default")
      (node (ref "C32") (pin "P$1") (pinfunction "1_P$1") (pintype "passive"))
      (node (ref "U3") (pin "20") (pinfunction "XCIN_20") (pintype "bidirectional"))
      (node (ref "X3") (pin "P$1") (pinfunction "P$1_P$1") (pintype "bidirectional"))
    )
    (net (code "166") (name "XCOUT") (class "Default")
      (node (ref "C37") (pin "P$1") (pinfunction "1_P$1") (pintype "passive"))
      (node (ref "U3") (pin "21") (pinfunction "XCOUT_21") (pintype "bidirectional"))
      (node (ref "X3") (pin "P$2") (pinfunction "P$2_P$2") (pintype "bidirectional"))
    )
    (net (code "167") (name "XII") (class "Default")
      (node (ref "C1") (pin "P$1") (pinfunction "1_P$1") (pintype "passive"))
      (node (ref "U1") (pin "8") (pinfunction "XI_8") (pintype "input"))
      (node (ref "X1") (pin "1") (pinfunction "1_1") (pintype "bidirectional"))
    )
    (net (code "168") (name "XOO") (class "Default")
      (node (ref "C2") (pin "P$1") (pinfunction "1_P$1") (pintype "passive"))
      (node (ref "U1") (pin "7") (pinfunction "XO_7") (pintype "output"))
      (node (ref "X1") (pin "3") (pinfunction "3_3") (pintype "bidirectional"))
    )
    (net (code "169") (name "XTAL1") (class "Default")
      (node (ref "C17") (pin "P$1") (pinfunction "1_P$1") (pintype "passive"))
      (node (ref "U3") (pin "23") (pinfunction "P2_13/XTAL_23") (pintype "bidirectional"))
      (node (ref "X2") (pin "1") (pinfunction "1_1") (pintype "bidirectional"))
    )
    (net (code "170") (name "XTAL2") (class "Default")
      (node (ref "C18") (pin "P$1") (pinfunction "1_P$1") (pintype "passive"))
      (node (ref "U3") (pin "24") (pinfunction "P2_12/EXTAL_24") (pintype "bidirectional"))
      (node (ref "X2") (pin "3") (pinfunction "3_3") (pintype "bidirectional"))
    )
    (net (code "171") (name "unconnected-(U3-VBAT-Pad18)") (class "Default")
      (node (ref "U3") (pin "18") (pinfunction "VBAT_18") (pintype "bidirectional"))
    )
  )
)
